# SCH_MCU.net
KiCad netlist of a schematic drawn in Altium Designer
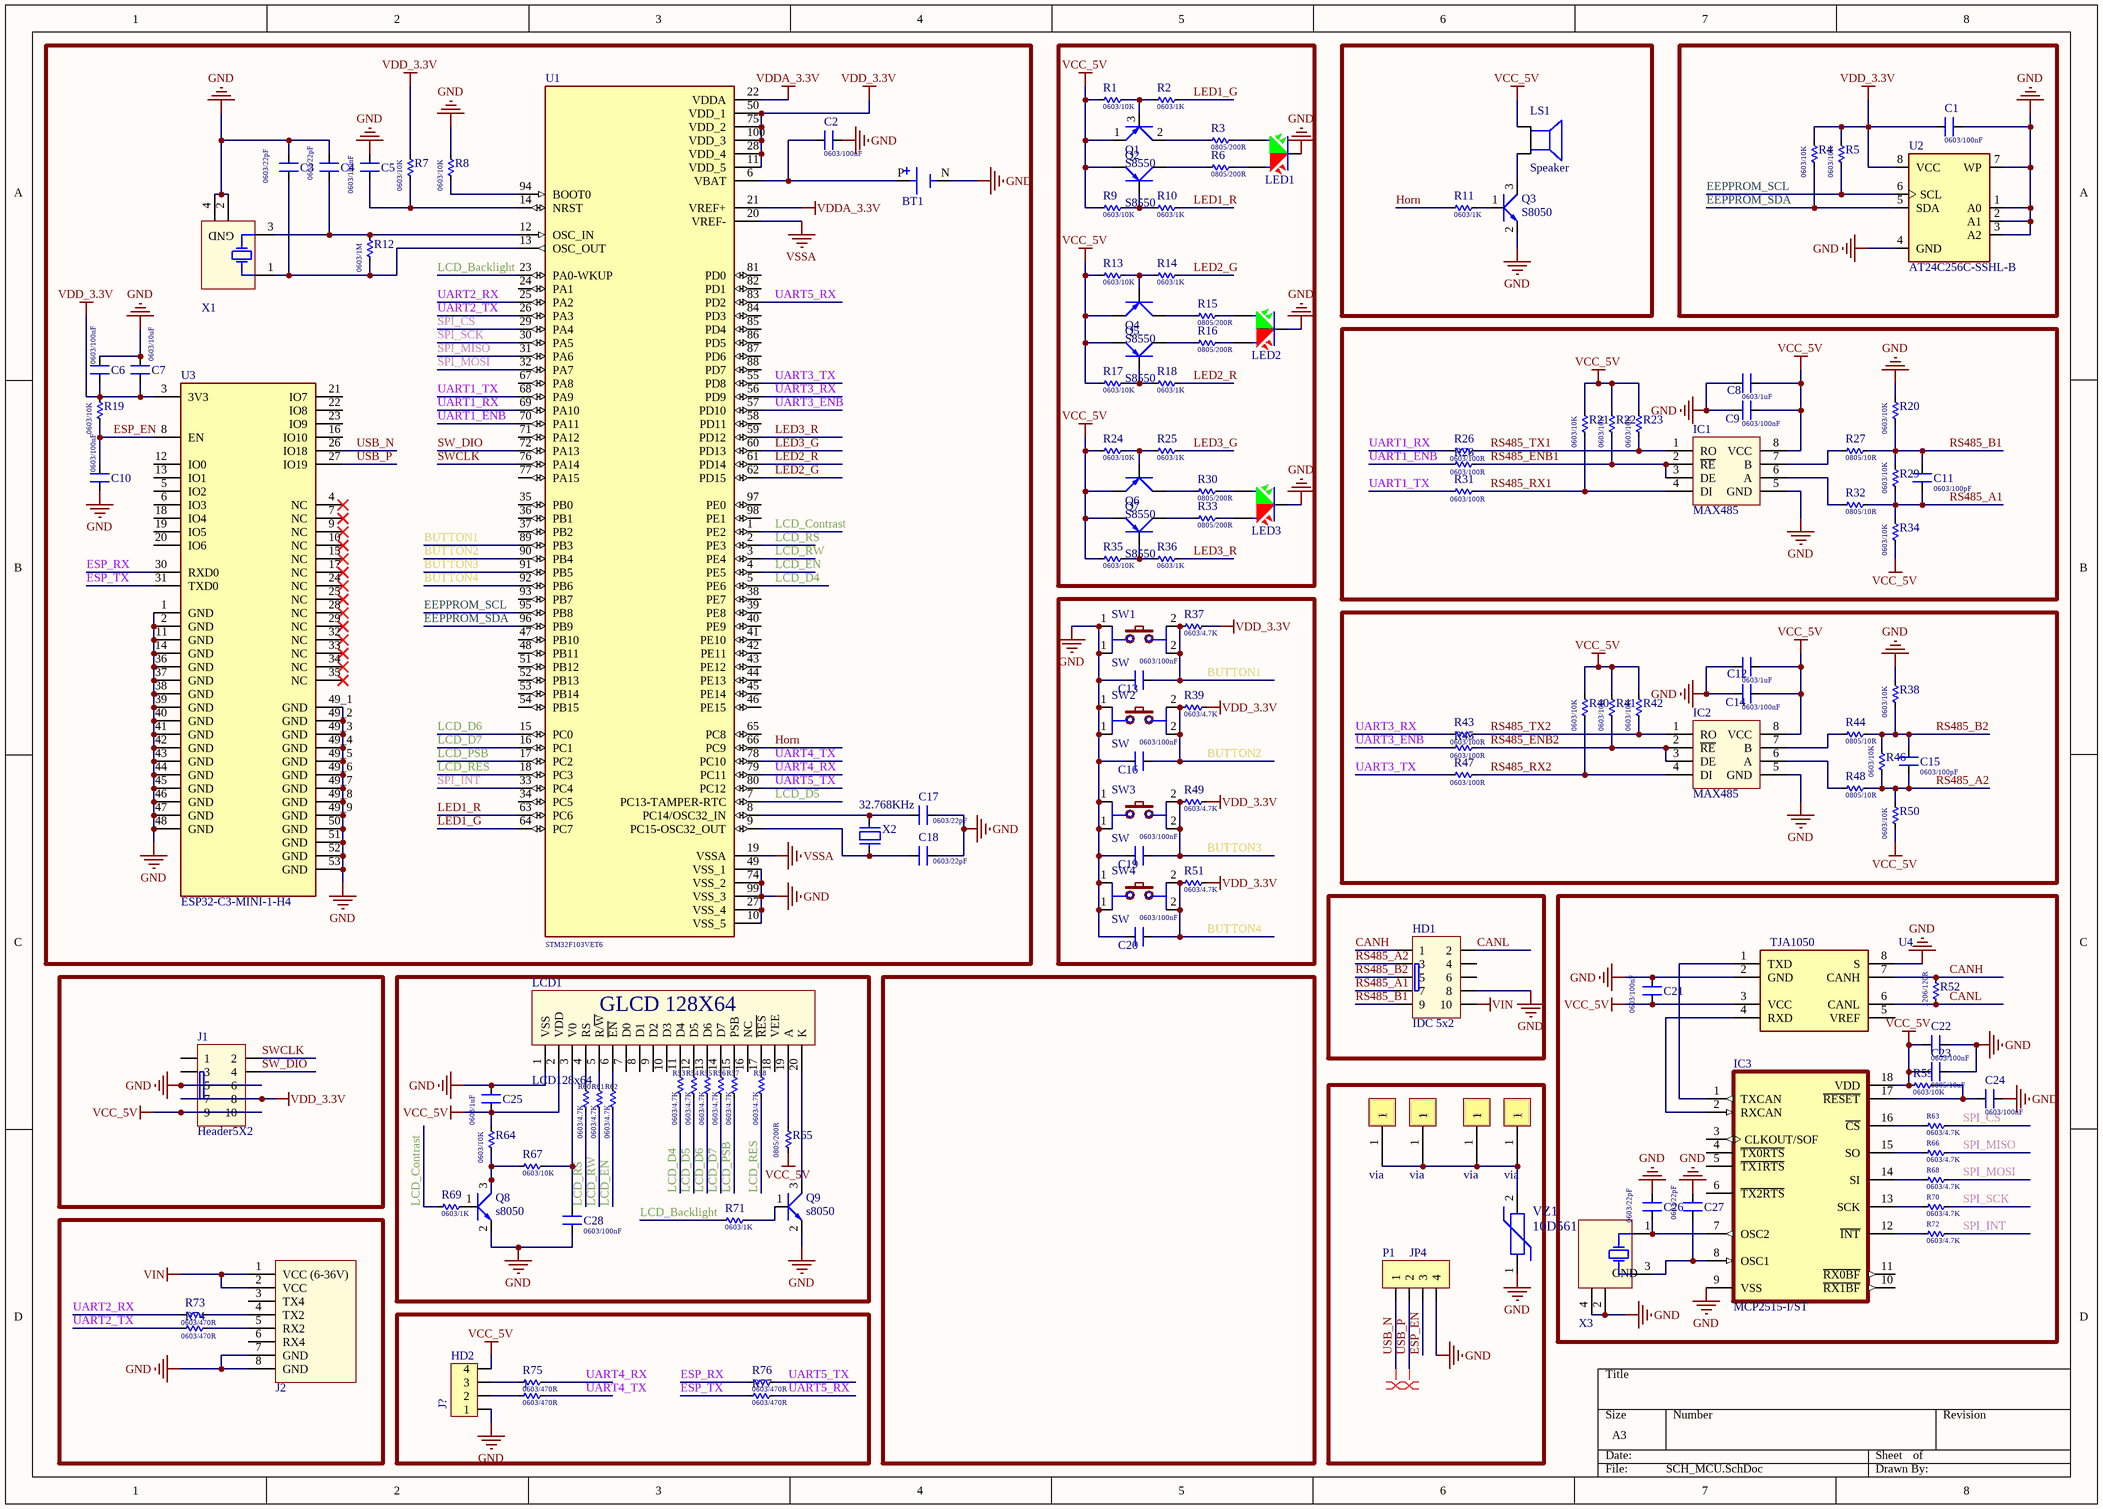
[diagram p0: SCH_MCU.SchDoc]

(export (version "E")
  (design (tool "Eeschema 10.0.6"))
  (components
    (comp (ref "1")
      (value "0603/470R")
      (footprint "RES-SMD-0603")
      (description "Resistor")
      (fields
        (field (name "MANUFACTURER") "Generic Components")
        (field (name "PUBLISHER") "Altium Hobart Technology Centre")
      )
      (libsource (lib "RAL") (part "Res-SMD"))
    )
    (comp (ref "BT1")
      (value "BATTERY")
      (footprint "BAT_CR2032-BS-6-1")
      (description "Battery base CR2032 SMD Battery Connectors ROHS")
      (fields (field (name "MP") "CR2032-BS-6-1") (field (name "MF") "Shenzhen Q&J Electronics Co. Ltd"))
      (libsource (lib "mySche") (part "CR2032-BS-6-1"))
    )
    (comp (ref "C1") (value "0603/100nF") (footprint "CAP-SMD-0603") (libsource (lib "RAL") (part "CAP-SMD")))
    (comp (ref "C2") (value "0603/100nF") (footprint "CAP-SMD-0603") (libsource (lib "RAL") (part "CAP-SMD")))
    (comp (ref "C3") (value "0603/22pF") (footprint "CAP-SMD-0603") (libsource (lib "RAL") (part "CAP-SMD")))
    (comp (ref "C4") (value "0603/22pF") (footprint "CAP-SMD-0603") (libsource (lib "RAL") (part "CAP-SMD")))
    (comp (ref "C5") (value "0603/100nF") (footprint "CAP-SMD-0603") (libsource (lib "RAL") (part "CAP-SMD")))
    (comp (ref "C6") (value "0603/100nF") (footprint "CAP-SMD-0603") (libsource (lib "RAL") (part "CAP-SMD")))
    (comp (ref "C7") (value "0603/10uF") (footprint "CAP-SMD-0603") (libsource (lib "RAL") (part "CAP-SMD")))
    (comp (ref "C8") (value "0603/1uF") (footprint "CAP-SMD-0603") (libsource (lib "RAL") (part "CAP-SMD")))
    (comp (ref "C9") (value "0603/100nF") (footprint "CAP-SMD-0603") (libsource (lib "RAL") (part "CAP-SMD")))
    (comp (ref "C10")
      (value "0603/100nF")
      (footprint "CAP-SMD-0603")
      (libsource (lib "RAL") (part "CAP-SMD"))
    )
    (comp (ref "C11")
      (value "0603/100pF")
      (footprint "CAP-SMD-0603")
      (libsource (lib "RAL") (part "CAP-SMD"))
    )
    (comp (ref "C12") (value "0603/1uF") (footprint "CAP-SMD-0603") (libsource (lib "RAL") (part "CAP-SMD")))
    (comp (ref "C13")
      (value "0603/100nF")
      (footprint "CAP-SMD-0603")
      (libsource (lib "RAL") (part "CAP-SMD"))
    )
    (comp (ref "C14")
      (value "0603/100nF")
      (footprint "CAP-SMD-0603")
      (libsource (lib "RAL") (part "CAP-SMD"))
    )
    (comp (ref "C15")
      (value "0603/100pF")
      (footprint "CAP-SMD-0603")
      (libsource (lib "RAL") (part "CAP-SMD"))
    )
    (comp (ref "C16")
      (value "0603/100nF")
      (footprint "CAP-SMD-0603")
      (libsource (lib "RAL") (part "CAP-SMD"))
    )
    (comp (ref "C17") (value "0603/22pF") (footprint "CAP-SMD-0603") (libsource (lib "RAL") (part "CAP-SMD")))
    (comp (ref "C18") (value "0603/22pF") (footprint "CAP-SMD-0603") (libsource (lib "RAL") (part "CAP-SMD")))
    (comp (ref "C19")
      (value "0603/100nF")
      (footprint "CAP-SMD-0603")
      (libsource (lib "RAL") (part "CAP-SMD"))
    )
    (comp (ref "C20")
      (value "0603/100nF")
      (footprint "CAP-SMD-0603")
      (libsource (lib "RAL") (part "CAP-SMD"))
    )
    (comp (ref "C21")
      (value "0603/100nF")
      (footprint "CAP-SMD-0603")
      (libsource (lib "RAL") (part "CAP-SMD"))
    )
    (comp (ref "C22")
      (value "0603/100nF")
      (footprint "CAP-SMD-0603")
      (libsource (lib "RAL") (part "CAP-SMD"))
    )
    (comp (ref "C23") (value "0805/10uF") (footprint "CAP-SMD-0805") (libsource (lib "RAL") (part "CAP-SMD")))
    (comp (ref "C24")
      (value "0603/100nF")
      (footprint "CAP-SMD-0603")
      (libsource (lib "RAL") (part "CAP-SMD"))
    )
    (comp (ref "C25") (value "0603/1uF") (footprint "CAP-SMD-0603") (libsource (lib "RAL") (part "CAP-SMD")))
    (comp (ref "C26") (value "0603/22pF") (footprint "CAP-SMD-0603") (libsource (lib "RAL") (part "CAP-SMD")))
    (comp (ref "C27") (value "0603/22pF") (footprint "CAP-SMD-0603") (libsource (lib "RAL") (part "CAP-SMD")))
    (comp (ref "C28")
      (value "0603/100nF")
      (footprint "CAP-SMD-0603")
      (libsource (lib "RAL") (part "CAP-SMD"))
    )
    (comp (ref "HD1")
      (value "IDC 5x2")
      (footprint "IDC10-BH")
      (libsource (lib "TechMT.VN_Lib_Project v2") (part "IDC 5X2"))
    )
    (comp (ref "HD2")
      (value "J?")
      (footprint "Header4")
      (description "Header IDC, 4 x 1 Pin Vertical 2.54mm Pitch (Non-Boxed, Male)")
      (fields
        (field (name "MANUFACTURER") "Würth Elektronik eiSos GmbH")
        (field (name "PARTNO") "613002143121")
        (field (name "CREATED BY") "Karrer Zheng")
      )
      (libsource (lib "TechMT.VN_Lib_Project v2") (part "Header4"))
    )
    (comp (ref "IC1")
      (value "MAX485")
      (footprint "SO8")
      (description "RS232 - RS485 (Same sn75176)")
      (libsource (lib "RAL") (part "IC MAX485"))
    )
    (comp (ref "IC2")
      (value "MAX485")
      (footprint "SO8")
      (description "RS232 - RS485 (Same sn75176)")
      (libsource (lib "RAL") (part "IC MAX485"))
    )
    (comp (ref "IC3")
      (value "MCP2515-I/ST")
      (footprint "SO18")
      (description "CAN 1Mbps Sleep/Standby 3.3V/5V 20-Pin TSSOP Tube")
      (fields (field (name "MF") "Microchip Technology"))
      (libsource (lib "lib") (part "MCP2515-I/ST"))
    )
    (comp (ref "J1") (value "Header5X2") (footprint "IDC10-BH") (libsource (lib "RAL") (part "Header5X2")))
    (comp (ref "J2") (value "8pin_2mm") (footprint "8PIN_2mm") (libsource (lib "mySche") (part "8pin_2mm")))
    (comp (ref "LCD1")
      (value "LCD128x64")
      (footprint "LCD128X64 ST7920")
      (description "LCD Graphic 128x64")
      (libsource (lib "lib") (part "LCD128x64"))
    )
    (comp (ref "LED1")
      (value "LED")
      (footprint "LED-32")
      (description "LED 2 colour Green and Red")
      (libsource (lib "RAL") (part "LED2"))
    )
    (comp (ref "LED2")
      (value "LED")
      (footprint "LED-32")
      (description "LED 2 colour Green and Red")
      (libsource (lib "RAL") (part "LED2"))
    )
    (comp (ref "LED3")
      (value "LED")
      (footprint "LED-32")
      (description "LED 2 colour Green and Red")
      (libsource (lib "RAL") (part "LED2"))
    )
    (comp (ref "LS1")
      (value "Speaker")
      (footprint "SPEAKER - 9*5.5")
      (description "Loudspeaker")
      (fields (field (name "PUBLISHER") "Altium Limited"))
      (libsource (lib "RAL") (part "Speaker"))
    )
    (comp (ref "P1")
      (value "JP4")
      (footprint "JP4-C1T")
      (description "WR-PHD 2.54 mm Angled Socket Header")
      (fields
        (field (name "MANUFACTURER") "Würth Elektronik eiSos GmbH")
        (field (name "PARTNO") "613004143121")
        (field (name "CREATED BY") "Karrer Zheng")
      )
      (libsource (lib "RAL") (part "JP4"))
    )
    (comp (ref "Q1")
      (value "S8550")
      (footprint "SOT23-321")
      (description "PNP 600mW, ECB")
      (libsource (lib "RAL") (part "BJT PNP"))
    )
    (comp (ref "Q2")
      (value "S8550")
      (footprint "SOT23-321")
      (description "PNP 600mW, ECB")
      (libsource (lib "") (part "BJT PNP_1"))
    )
    (comp (ref "Q3")
      (value "S8050")
      (footprint "SOT23-132")
      (description "NPN 600mW, ECB")
      (libsource (lib "RAL") (part "BJT NPN"))
    )
    (comp (ref "Q4")
      (value "S8550")
      (footprint "SOT23-321")
      (description "PNP 600mW, ECB")
      (libsource (lib "") (part "BJT PNP_1"))
    )
    (comp (ref "Q5")
      (value "S8550")
      (footprint "SOT23-321")
      (description "PNP 600mW, ECB")
      (libsource (lib "") (part "BJT PNP_1"))
    )
    (comp (ref "Q6")
      (value "S8550")
      (footprint "SOT23-321")
      (description "PNP 600mW, ECB")
      (libsource (lib "") (part "BJT PNP_1"))
    )
    (comp (ref "Q7")
      (value "S8550")
      (footprint "SOT23-321")
      (description "PNP 600mW, ECB")
      (libsource (lib "") (part "BJT PNP_1"))
    )
    (comp (ref "Q8")
      (value "s8050")
      (footprint "SOT23-132")
      (description "NPN 600mW, ECB")
      (libsource (lib "RAL") (part "BJT NPN"))
    )
    (comp (ref "Q9")
      (value "s8050")
      (footprint "SOT23-132")
      (description "NPN 600mW, ECB")
      (libsource (lib "RAL") (part "BJT NPN"))
    )
    (comp (ref "R1")
      (value "0603/10K")
      (footprint "RES-SMD-0603")
      (description "Resistor")
      (fields
        (field (name "MANUFACTURER") "Generic Components")
        (field (name "PUBLISHER") "Altium Hobart Technology Centre")
      )
      (libsource (lib "RAL") (part "Res-SMD"))
    )
    (comp (ref "R2")
      (value "0603/1K")
      (footprint "RES-SMD-0603")
      (description "Resistor")
      (fields
        (field (name "MANUFACTURER") "Generic Components")
        (field (name "PUBLISHER") "Altium Hobart Technology Centre")
      )
      (libsource (lib "RAL") (part "Res-SMD"))
    )
    (comp (ref "R3")
      (value "0805/200R")
      (footprint "RES-SMD-0805")
      (description "Resistor")
      (fields
        (field (name "MANUFACTURER") "Generic Components")
        (field (name "PUBLISHER") "Altium Hobart Technology Centre")
      )
      (libsource (lib "RAL") (part "Res-SMD"))
    )
    (comp (ref "R4")
      (value "0603/10K")
      (footprint "RES-SMD-0603")
      (description "Resistor")
      (fields
        (field (name "MANUFACTURER") "Generic Components")
        (field (name "PUBLISHER") "Altium Hobart Technology Centre")
      )
      (libsource (lib "RAL") (part "Res-SMD"))
    )
    (comp (ref "R5")
      (value "0603/10K")
      (footprint "RES-SMD-0603")
      (description "Resistor")
      (fields
        (field (name "MANUFACTURER") "Generic Components")
        (field (name "PUBLISHER") "Altium Hobart Technology Centre")
      )
      (libsource (lib "RAL") (part "Res-SMD"))
    )
    (comp (ref "R6")
      (value "0805/200R")
      (footprint "RES-SMD-0805")
      (description "Resistor")
      (fields
        (field (name "MANUFACTURER") "Generic Components")
        (field (name "PUBLISHER") "Altium Hobart Technology Centre")
      )
      (libsource (lib "RAL") (part "Res-SMD"))
    )
    (comp (ref "R7")
      (value "0603/10K")
      (footprint "RES-SMD-0603")
      (description "Resistor")
      (fields
        (field (name "MANUFACTURER") "Generic Components")
        (field (name "PUBLISHER") "Altium Hobart Technology Centre")
      )
      (libsource (lib "RAL") (part "Res-SMD"))
    )
    (comp (ref "R8")
      (value "0603/10K")
      (footprint "RES-SMD-0603")
      (description "Resistor")
      (fields
        (field (name "MANUFACTURER") "Generic Components")
        (field (name "PUBLISHER") "Altium Hobart Technology Centre")
      )
      (libsource (lib "RAL") (part "Res-SMD"))
    )
    (comp (ref "R9")
      (value "0603/10K")
      (footprint "RES-SMD-0603")
      (description "Resistor")
      (fields
        (field (name "MANUFACTURER") "Generic Components")
        (field (name "PUBLISHER") "Altium Hobart Technology Centre")
      )
      (libsource (lib "RAL") (part "Res-SMD"))
    )
    (comp (ref "R10")
      (value "0603/1K")
      (footprint "RES-SMD-0603")
      (description "Resistor")
      (fields
        (field (name "MANUFACTURER") "Generic Components")
        (field (name "PUBLISHER") "Altium Hobart Technology Centre")
      )
      (libsource (lib "RAL") (part "Res-SMD"))
    )
    (comp (ref "R11")
      (value "0603/1K")
      (footprint "RES-SMD-0603")
      (description "Resistor")
      (fields
        (field (name "MANUFACTURER") "Generic Components")
        (field (name "PUBLISHER") "Altium Hobart Technology Centre")
      )
      (libsource (lib "RAL") (part "Res-SMD"))
    )
    (comp (ref "R12")
      (value "0603/1M")
      (footprint "RES-SMD-0603")
      (description "Resistor")
      (fields
        (field (name "MANUFACTURER") "Generic Components")
        (field (name "PUBLISHER") "Altium Hobart Technology Centre")
      )
      (libsource (lib "RAL") (part "Res-SMD"))
    )
    (comp (ref "R13")
      (value "0603/10K")
      (footprint "RES-SMD-0603")
      (description "Resistor")
      (fields
        (field (name "MANUFACTURER") "Generic Components")
        (field (name "PUBLISHER") "Altium Hobart Technology Centre")
      )
      (libsource (lib "RAL") (part "Res-SMD"))
    )
    (comp (ref "R14")
      (value "0603/1K")
      (footprint "RES-SMD-0603")
      (description "Resistor")
      (fields
        (field (name "MANUFACTURER") "Generic Components")
        (field (name "PUBLISHER") "Altium Hobart Technology Centre")
      )
      (libsource (lib "RAL") (part "Res-SMD"))
    )
    (comp (ref "R15")
      (value "0805/200R")
      (footprint "RES-SMD-0805")
      (description "Resistor")
      (fields
        (field (name "MANUFACTURER") "Generic Components")
        (field (name "PUBLISHER") "Altium Hobart Technology Centre")
      )
      (libsource (lib "RAL") (part "Res-SMD"))
    )
    (comp (ref "R16")
      (value "0805/200R")
      (footprint "RES-SMD-0805")
      (description "Resistor")
      (fields
        (field (name "MANUFACTURER") "Generic Components")
        (field (name "PUBLISHER") "Altium Hobart Technology Centre")
      )
      (libsource (lib "RAL") (part "Res-SMD"))
    )
    (comp (ref "R17")
      (value "0603/10K")
      (footprint "RES-SMD-0603")
      (description "Resistor")
      (fields
        (field (name "MANUFACTURER") "Generic Components")
        (field (name "PUBLISHER") "Altium Hobart Technology Centre")
      )
      (libsource (lib "RAL") (part "Res-SMD"))
    )
    (comp (ref "R18")
      (value "0603/1K")
      (footprint "RES-SMD-0603")
      (description "Resistor")
      (fields
        (field (name "MANUFACTURER") "Generic Components")
        (field (name "PUBLISHER") "Altium Hobart Technology Centre")
      )
      (libsource (lib "RAL") (part "Res-SMD"))
    )
    (comp (ref "R19")
      (value "0603/10K")
      (footprint "RES-SMD-0603")
      (description "Resistor")
      (fields
        (field (name "MANUFACTURER") "Generic Components")
        (field (name "PUBLISHER") "Altium Hobart Technology Centre")
      )
      (libsource (lib "RAL") (part "Res-SMD"))
    )
    (comp (ref "R20")
      (value "0603/10K")
      (footprint "RES-SMD-0603")
      (description "Resistor")
      (fields
        (field (name "MANUFACTURER") "Generic Components")
        (field (name "PUBLISHER") "Altium Hobart Technology Centre")
      )
      (libsource (lib "RAL") (part "Res-SMD"))
    )
    (comp (ref "R21")
      (value "0603/10K")
      (footprint "RES-SMD-0603")
      (description "Resistor")
      (fields
        (field (name "MANUFACTURER") "Generic Components")
        (field (name "PUBLISHER") "Altium Hobart Technology Centre")
      )
      (libsource (lib "RAL") (part "Res-SMD"))
    )
    (comp (ref "R22")
      (value "0603/10K")
      (footprint "RES-SMD-0603")
      (description "Resistor")
      (fields
        (field (name "MANUFACTURER") "Generic Components")
        (field (name "PUBLISHER") "Altium Hobart Technology Centre")
      )
      (libsource (lib "RAL") (part "Res-SMD"))
    )
    (comp (ref "R23")
      (value "0603/10K")
      (footprint "RES-SMD-0603")
      (description "Resistor")
      (fields
        (field (name "MANUFACTURER") "Generic Components")
        (field (name "PUBLISHER") "Altium Hobart Technology Centre")
      )
      (libsource (lib "RAL") (part "Res-SMD"))
    )
    (comp (ref "R24")
      (value "0603/10K")
      (footprint "RES-SMD-0603")
      (description "Resistor")
      (fields
        (field (name "MANUFACTURER") "Generic Components")
        (field (name "PUBLISHER") "Altium Hobart Technology Centre")
      )
      (libsource (lib "RAL") (part "Res-SMD"))
    )
    (comp (ref "R25")
      (value "0603/1K")
      (footprint "RES-SMD-0603")
      (description "Resistor")
      (fields
        (field (name "MANUFACTURER") "Generic Components")
        (field (name "PUBLISHER") "Altium Hobart Technology Centre")
      )
      (libsource (lib "RAL") (part "Res-SMD"))
    )
    (comp (ref "R26")
      (value "0603/100R")
      (footprint "RES-SMD-0603")
      (description "Resistor")
      (fields
        (field (name "MANUFACTURER") "Generic Components")
        (field (name "PUBLISHER") "Altium Hobart Technology Centre")
      )
      (libsource (lib "RAL") (part "Res-SMD"))
    )
    (comp (ref "R27")
      (value "0805/10R")
      (footprint "RES-SMD-0805")
      (description "Resistor")
      (fields
        (field (name "MANUFACTURER") "Generic Components")
        (field (name "PUBLISHER") "Altium Hobart Technology Centre")
      )
      (libsource (lib "RAL") (part "Res-SMD"))
    )
    (comp (ref "R28")
      (value "0603/100R")
      (footprint "RES-SMD-0603")
      (description "Resistor")
      (fields
        (field (name "MANUFACTURER") "Generic Components")
        (field (name "PUBLISHER") "Altium Hobart Technology Centre")
      )
      (libsource (lib "RAL") (part "Res-SMD"))
    )
    (comp (ref "R29")
      (value "0603/10K")
      (footprint "RES-SMD-0603")
      (description "Resistor")
      (fields
        (field (name "MANUFACTURER") "Generic Components")
        (field (name "PUBLISHER") "Altium Hobart Technology Centre")
      )
      (libsource (lib "RAL") (part "Res-SMD"))
    )
    (comp (ref "R30")
      (value "0805/200R")
      (footprint "RES-SMD-0805")
      (description "Resistor")
      (fields
        (field (name "MANUFACTURER") "Generic Components")
        (field (name "PUBLISHER") "Altium Hobart Technology Centre")
      )
      (libsource (lib "RAL") (part "Res-SMD"))
    )
    (comp (ref "R31")
      (value "0603/100R")
      (footprint "RES-SMD-0603")
      (description "Resistor")
      (fields
        (field (name "MANUFACTURER") "Generic Components")
        (field (name "PUBLISHER") "Altium Hobart Technology Centre")
      )
      (libsource (lib "RAL") (part "Res-SMD"))
    )
    (comp (ref "R32")
      (value "0805/10R")
      (footprint "RES-SMD-0805")
      (description "Resistor")
      (fields
        (field (name "MANUFACTURER") "Generic Components")
        (field (name "PUBLISHER") "Altium Hobart Technology Centre")
      )
      (libsource (lib "RAL") (part "Res-SMD"))
    )
    (comp (ref "R33")
      (value "0805/200R")
      (footprint "RES-SMD-0805")
      (description "Resistor")
      (fields
        (field (name "MANUFACTURER") "Generic Components")
        (field (name "PUBLISHER") "Altium Hobart Technology Centre")
      )
      (libsource (lib "RAL") (part "Res-SMD"))
    )
    (comp (ref "R34")
      (value "0603/10K")
      (footprint "RES-SMD-0603")
      (description "Resistor")
      (fields
        (field (name "MANUFACTURER") "Generic Components")
        (field (name "PUBLISHER") "Altium Hobart Technology Centre")
      )
      (libsource (lib "RAL") (part "Res-SMD"))
    )
    (comp (ref "R35")
      (value "0603/10K")
      (footprint "RES-SMD-0603")
      (description "Resistor")
      (fields
        (field (name "MANUFACTURER") "Generic Components")
        (field (name "PUBLISHER") "Altium Hobart Technology Centre")
      )
      (libsource (lib "RAL") (part "Res-SMD"))
    )
    (comp (ref "R36")
      (value "0603/1K")
      (footprint "RES-SMD-0603")
      (description "Resistor")
      (fields
        (field (name "MANUFACTURER") "Generic Components")
        (field (name "PUBLISHER") "Altium Hobart Technology Centre")
      )
      (libsource (lib "RAL") (part "Res-SMD"))
    )
    (comp (ref "R37")
      (value "0603/4.7K")
      (footprint "RES-SMD-0603")
      (description "Resistor")
      (fields
        (field (name "MANUFACTURER") "Generic Components")
        (field (name "PUBLISHER") "Altium Hobart Technology Centre")
      )
      (libsource (lib "RAL") (part "Res-SMD"))
    )
    (comp (ref "R38")
      (value "0603/10K")
      (footprint "RES-SMD-0603")
      (description "Resistor")
      (fields
        (field (name "MANUFACTURER") "Generic Components")
        (field (name "PUBLISHER") "Altium Hobart Technology Centre")
      )
      (libsource (lib "RAL") (part "Res-SMD"))
    )
    (comp (ref "R39")
      (value "0603/4.7K")
      (footprint "RES-SMD-0603")
      (description "Resistor")
      (fields
        (field (name "MANUFACTURER") "Generic Components")
        (field (name "PUBLISHER") "Altium Hobart Technology Centre")
      )
      (libsource (lib "RAL") (part "Res-SMD"))
    )
    (comp (ref "R40")
      (value "0603/10K")
      (footprint "RES-SMD-0603")
      (description "Resistor")
      (fields
        (field (name "MANUFACTURER") "Generic Components")
        (field (name "PUBLISHER") "Altium Hobart Technology Centre")
      )
      (libsource (lib "RAL") (part "Res-SMD"))
    )
    (comp (ref "R41")
      (value "0603/10K")
      (footprint "RES-SMD-0603")
      (description "Resistor")
      (fields
        (field (name "MANUFACTURER") "Generic Components")
        (field (name "PUBLISHER") "Altium Hobart Technology Centre")
      )
      (libsource (lib "RAL") (part "Res-SMD"))
    )
    (comp (ref "R42")
      (value "0603/10K")
      (footprint "RES-SMD-0603")
      (description "Resistor")
      (fields
        (field (name "MANUFACTURER") "Generic Components")
        (field (name "PUBLISHER") "Altium Hobart Technology Centre")
      )
      (libsource (lib "RAL") (part "Res-SMD"))
    )
    (comp (ref "R43")
      (value "0603/100R")
      (footprint "RES-SMD-0603")
      (description "Resistor")
      (fields
        (field (name "MANUFACTURER") "Generic Components")
        (field (name "PUBLISHER") "Altium Hobart Technology Centre")
      )
      (libsource (lib "RAL") (part "Res-SMD"))
    )
    (comp (ref "R44")
      (value "0805/10R")
      (footprint "RES-SMD-0805")
      (description "Resistor")
      (fields
        (field (name "MANUFACTURER") "Generic Components")
        (field (name "PUBLISHER") "Altium Hobart Technology Centre")
      )
      (libsource (lib "RAL") (part "Res-SMD"))
    )
    (comp (ref "R45")
      (value "0603/100R")
      (footprint "RES-SMD-0603")
      (description "Resistor")
      (fields
        (field (name "MANUFACTURER") "Generic Components")
        (field (name "PUBLISHER") "Altium Hobart Technology Centre")
      )
      (libsource (lib "RAL") (part "Res-SMD"))
    )
    (comp (ref "R46")
      (value "0603/10K")
      (footprint "RES-SMD-0603")
      (description "Resistor")
      (fields
        (field (name "MANUFACTURER") "Generic Components")
        (field (name "PUBLISHER") "Altium Hobart Technology Centre")
      )
      (libsource (lib "RAL") (part "Res-SMD"))
    )
    (comp (ref "R47")
      (value "0603/100R")
      (footprint "RES-SMD-0603")
      (description "Resistor")
      (fields
        (field (name "MANUFACTURER") "Generic Components")
        (field (name "PUBLISHER") "Altium Hobart Technology Centre")
      )
      (libsource (lib "RAL") (part "Res-SMD"))
    )
    (comp (ref "R48")
      (value "0805/10R")
      (footprint "RES-SMD-0805")
      (description "Resistor")
      (fields
        (field (name "MANUFACTURER") "Generic Components")
        (field (name "PUBLISHER") "Altium Hobart Technology Centre")
      )
      (libsource (lib "RAL") (part "Res-SMD"))
    )
    (comp (ref "R49")
      (value "0603/4.7K")
      (footprint "RES-SMD-0603")
      (description "Resistor")
      (fields
        (field (name "MANUFACTURER") "Generic Components")
        (field (name "PUBLISHER") "Altium Hobart Technology Centre")
      )
      (libsource (lib "RAL") (part "Res-SMD"))
    )
    (comp (ref "R50")
      (value "0603/10K")
      (footprint "RES-SMD-0603")
      (description "Resistor")
      (fields
        (field (name "MANUFACTURER") "Generic Components")
        (field (name "PUBLISHER") "Altium Hobart Technology Centre")
      )
      (libsource (lib "RAL") (part "Res-SMD"))
    )
    (comp (ref "R51")
      (value "0603/4.7K")
      (footprint "RES-SMD-0603")
      (description "Resistor")
      (fields
        (field (name "MANUFACTURER") "Generic Components")
        (field (name "PUBLISHER") "Altium Hobart Technology Centre")
      )
      (libsource (lib "RAL") (part "Res-SMD"))
    )
    (comp (ref "R52")
      (value "1206/120R")
      (footprint "RES-SMD-0603")
      (description "Resistor")
      (fields
        (field (name "MANUFACTURER") "Generic Components")
        (field (name "PUBLISHER") "Altium Hobart Technology Centre")
      )
      (libsource (lib "RAL") (part "Res-SMD"))
    )
    (comp (ref "R53")
      (value "0603/4.7K")
      (footprint "RES-SMD-0603")
      (description "Resistor")
      (fields
        (field (name "MANUFACTURER") "Generic Components")
        (field (name "PUBLISHER") "Altium Hobart Technology Centre")
      )
      (libsource (lib "RAL") (part "Res-SMD"))
    )
    (comp (ref "R54")
      (value "0603/4.7K")
      (footprint "RES-SMD-0603")
      (description "Resistor")
      (fields
        (field (name "MANUFACTURER") "Generic Components")
        (field (name "PUBLISHER") "Altium Hobart Technology Centre")
      )
      (libsource (lib "RAL") (part "Res-SMD"))
    )
    (comp (ref "R55")
      (value "0603/4.7K")
      (footprint "RES-SMD-0603")
      (description "Resistor")
      (fields
        (field (name "MANUFACTURER") "Generic Components")
        (field (name "PUBLISHER") "Altium Hobart Technology Centre")
      )
      (libsource (lib "RAL") (part "Res-SMD"))
    )
    (comp (ref "R56")
      (value "0603/4.7K")
      (footprint "RES-SMD-0603")
      (description "Resistor")
      (fields
        (field (name "MANUFACTURER") "Generic Components")
        (field (name "PUBLISHER") "Altium Hobart Technology Centre")
      )
      (libsource (lib "RAL") (part "Res-SMD"))
    )
    (comp (ref "R57")
      (value "0603/4.7K")
      (footprint "RES-SMD-0603")
      (description "Resistor")
      (fields
        (field (name "MANUFACTURER") "Generic Components")
        (field (name "PUBLISHER") "Altium Hobart Technology Centre")
      )
      (libsource (lib "RAL") (part "Res-SMD"))
    )
    (comp (ref "R58")
      (value "0603/4.7K")
      (footprint "RES-SMD-0603")
      (description "Resistor")
      (fields
        (field (name "MANUFACTURER") "Generic Components")
        (field (name "PUBLISHER") "Altium Hobart Technology Centre")
      )
      (libsource (lib "RAL") (part "Res-SMD"))
    )
    (comp (ref "R59")
      (value "0603/10K")
      (footprint "RES-SMD-0603")
      (description "Resistor")
      (fields
        (field (name "MANUFACTURER") "Generic Components")
        (field (name "PUBLISHER") "Altium Hobart Technology Centre")
      )
      (libsource (lib "RAL") (part "Res-SMD"))
    )
    (comp (ref "R60")
      (value "0603/4.7K")
      (footprint "RES-SMD-0603")
      (description "Resistor")
      (fields
        (field (name "MANUFACTURER") "Generic Components")
        (field (name "PUBLISHER") "Altium Hobart Technology Centre")
      )
      (libsource (lib "RAL") (part "Res-SMD"))
    )
    (comp (ref "R61")
      (value "0603/4.7K")
      (footprint "RES-SMD-0603")
      (description "Resistor")
      (fields
        (field (name "MANUFACTURER") "Generic Components")
        (field (name "PUBLISHER") "Altium Hobart Technology Centre")
      )
      (libsource (lib "RAL") (part "Res-SMD"))
    )
    (comp (ref "R62")
      (value "0603/4.7K")
      (footprint "RES-SMD-0603")
      (description "Resistor")
      (fields
        (field (name "MANUFACTURER") "Generic Components")
        (field (name "PUBLISHER") "Altium Hobart Technology Centre")
      )
      (libsource (lib "RAL") (part "Res-SMD"))
    )
    (comp (ref "R63")
      (value "0603/4.7K")
      (footprint "RES-SMD-0603")
      (description "Resistor")
      (fields
        (field (name "MANUFACTURER") "Generic Components")
        (field (name "PUBLISHER") "Altium Hobart Technology Centre")
      )
      (libsource (lib "RAL") (part "Res-SMD"))
    )
    (comp (ref "R64")
      (value "0603/10K")
      (footprint "RES-SMD-0603")
      (description "Resistor")
      (fields
        (field (name "MANUFACTURER") "Generic Components")
        (field (name "PUBLISHER") "Altium Hobart Technology Centre")
      )
      (libsource (lib "RAL") (part "Res-SMD"))
    )
    (comp (ref "R65")
      (value "0805/200R")
      (footprint "RES-SMD-0805")
      (description "Resistor")
      (fields
        (field (name "MANUFACTURER") "Generic Components")
        (field (name "PUBLISHER") "Altium Hobart Technology Centre")
      )
      (libsource (lib "RAL") (part "Res-SMD"))
    )
    (comp (ref "R66")
      (value "0603/4.7K")
      (footprint "RES-SMD-0603")
      (description "Resistor")
      (fields
        (field (name "MANUFACTURER") "Generic Components")
        (field (name "PUBLISHER") "Altium Hobart Technology Centre")
      )
      (libsource (lib "RAL") (part "Res-SMD"))
    )
    (comp (ref "R67")
      (value "0603/10K")
      (footprint "RES-SMD-0603")
      (description "Resistor")
      (fields
        (field (name "MANUFACTURER") "Generic Components")
        (field (name "PUBLISHER") "Altium Hobart Technology Centre")
      )
      (libsource (lib "RAL") (part "Res-SMD"))
    )
    (comp (ref "R68")
      (value "0603/4.7K")
      (footprint "RES-SMD-0603")
      (description "Resistor")
      (fields
        (field (name "MANUFACTURER") "Generic Components")
        (field (name "PUBLISHER") "Altium Hobart Technology Centre")
      )
      (libsource (lib "RAL") (part "Res-SMD"))
    )
    (comp (ref "R69")
      (value "0603/1K")
      (footprint "RES-SMD-0603")
      (description "Resistor")
      (fields
        (field (name "MANUFACTURER") "Generic Components")
        (field (name "PUBLISHER") "Altium Hobart Technology Centre")
      )
      (libsource (lib "RAL") (part "Res-SMD"))
    )
    (comp (ref "R70")
      (value "0603/4.7K")
      (footprint "RES-SMD-0603")
      (description "Resistor")
      (fields
        (field (name "MANUFACTURER") "Generic Components")
        (field (name "PUBLISHER") "Altium Hobart Technology Centre")
      )
      (libsource (lib "RAL") (part "Res-SMD"))
    )
    (comp (ref "R71")
      (value "0603/1K")
      (footprint "RES-SMD-0603")
      (description "Resistor")
      (fields
        (field (name "MANUFACTURER") "Generic Components")
        (field (name "PUBLISHER") "Altium Hobart Technology Centre")
      )
      (libsource (lib "RAL") (part "Res-SMD"))
    )
    (comp (ref "R72")
      (value "0603/4.7K")
      (footprint "RES-SMD-0603")
      (description "Resistor")
      (fields
        (field (name "MANUFACTURER") "Generic Components")
        (field (name "PUBLISHER") "Altium Hobart Technology Centre")
      )
      (libsource (lib "RAL") (part "Res-SMD"))
    )
    (comp (ref "R73")
      (value "0603/470R")
      (footprint "RES-SMD-0603")
      (description "Resistor")
      (fields
        (field (name "MANUFACTURER") "Generic Components")
        (field (name "PUBLISHER") "Altium Hobart Technology Centre")
      )
      (libsource (lib "RAL") (part "Res-SMD"))
    )
    (comp (ref "R74")
      (value "0603/470R")
      (footprint "RES-SMD-0603")
      (description "Resistor")
      (fields
        (field (name "MANUFACTURER") "Generic Components")
        (field (name "PUBLISHER") "Altium Hobart Technology Centre")
      )
      (libsource (lib "RAL") (part "Res-SMD"))
    )
    (comp (ref "R75")
      (value "0603/470R")
      (footprint "RES-SMD-0603")
      (description "Resistor")
      (fields
        (field (name "MANUFACTURER") "Generic Components")
        (field (name "PUBLISHER") "Altium Hobart Technology Centre")
      )
      (libsource (lib "RAL") (part "Res-SMD"))
    )
    (comp (ref "R76")
      (value "0603/470R")
      (footprint "RES-SMD-0603")
      (description "Resistor")
      (fields
        (field (name "MANUFACTURER") "Generic Components")
        (field (name "PUBLISHER") "Altium Hobart Technology Centre")
      )
      (libsource (lib "RAL") (part "Res-SMD"))
    )
    (comp (ref "R77")
      (value "0603/470R")
      (footprint "RES-SMD-0603")
      (description "Resistor")
      (fields
        (field (name "MANUFACTURER") "Generic Components")
        (field (name "PUBLISHER") "Altium Hobart Technology Centre")
      )
      (libsource (lib "RAL") (part "Res-SMD"))
    )
    (comp (ref "SW1")
      (value "SW")
      (footprint "BUTTON-12x12")
      (description "Switch button 4 pin")
      (libsource (lib "RAL") (part "SW4"))
    )
    (comp (ref "SW2")
      (value "SW")
      (footprint "BUTTON-12x12")
      (description "Switch button 4 pin")
      (libsource (lib "RAL") (part "SW4"))
    )
    (comp (ref "SW3")
      (value "SW")
      (footprint "BUTTON-12x12")
      (description "Switch button 4 pin")
      (libsource (lib "RAL") (part "SW4"))
    )
    (comp (ref "SW4")
      (value "SW")
      (footprint "BUTTON-12x12")
      (description "Switch button 4 pin")
      (libsource (lib "RAL") (part "SW4"))
    )
    (comp (ref "U1")
      (value "STM32F103VET6")
      (footprint "QFP50P1600X1600X160-100N")
      (description "ARMÂ® CortexÂ®-M3 STM32F1 Microcontroller IC 32-Bit 72MHz 512KB (512K x 8) FLASH 100-LQFP (14x14)")
      (fields (field (name "MF") "STMicroelectronics"))
      (libsource (lib "lib") (part "STM32F103VET6"))
    )
    (comp (ref "U2")
      (value "AT24C256C-SSHL-B")
      (footprint "SO8")
      (description "EEPROM Serial-2Wire 256K-bit 32K x 8 1.8V/2.5V/3.3V/5V Automotive 8-Pin SOIC N Tube")
      (fields (field (name "MF") "Microchip Technology"))
      (libsource (lib "lib") (part "AT24C256C-SSHL-B"))
    )
    (comp (ref "U3")
      (value "ESP32-C3-MINI-1-H4")
      (footprint "ESP32-C3-MINI-1-H4")
      (libsource (lib "RAL") (part "ESP32-C3-MINI-1-H4"))
    )
    (comp (ref "U4")
      (value "TJA1050")
      (footprint "SO8")
      (description "CAN 1MBd Silent 5V Automotive 8-Pin SO T/R")
      (fields (field (name "MF") "NXP Semiconductors"))
      (libsource (lib "lib") (part "TJA1050"))
    )
    (comp (ref "via1") (value "via") (footprint "VIA_LO") (libsource (lib "mySche") (part "Vit oc")))
    (comp (ref "via2") (value "via") (footprint "VIA_LO") (libsource (lib "mySche") (part "Vit oc")))
    (comp (ref "via3") (value "via") (footprint "VIA_LO") (libsource (lib "mySche") (part "Vit oc")))
    (comp (ref "via4") (value "via") (footprint "VIA_LO") (libsource (lib "mySche") (part "Vit oc")))
    (comp (ref "VZ1")
      (value "10D561")
      (footprint "Varistor 7K561 5mm")
      (description "Varistor")
      (fields (field (name "PUBLISHER") "Altium Limited"))
      (libsource (lib "RAL") (part "VAR"))
    )
    (comp (ref "X1")
      (value "16MHz")
      (footprint "XT4-16.000MHz-4_V")
      (description "Crystal, 16 MHz, -30 to 85 degC, 3.2 x 2.5 x 0.9 mm SMD")
      (libsource (lib "RAL") (part "XT4"))
    )
    (comp (ref "X2")
      (value "32.768KHz")
      (footprint "XT2-32.768KHz-2_V")
      (description "Crystal, 32.768 KHz, -40 to 85 degC, 3.2 x 1.5 x 0.9 mm SMD")
      (libsource (lib "RAL") (part "XT2"))
    )
    (comp (ref "X3")
      (value "8MHz")
      (footprint "XT4-16.000MHz-4_V")
      (description "Crystal, 16 MHz, -30 to 85 degC, 3.2 x 2.5 x 0.9 mm SMD")
      (libsource (lib "") (part "XT4_1"))
    )
  )
  (nets
    (net (code "1") (name "/BUTTON1") (class "Default")
      (node (ref "C13") (pin "2") (pinfunction "2_2") (pintype "passive"))
      (node (ref "R37") (pin "1") (pinfunction "1_1") (pintype "passive"))
      (node (ref "SW1") (pin "2") (pinfunction "2_2") (pintype "passive"))
      (node (ref "U1") (pin "89") (pinfunction "PB3_89") (pintype "bidirectional"))
    )
    (net (code "2") (name "/BUTTON2") (class "Default")
      (node (ref "C16") (pin "2") (pinfunction "2_2") (pintype "passive"))
      (node (ref "R39") (pin "1") (pinfunction "1_1") (pintype "passive"))
      (node (ref "SW2") (pin "2") (pinfunction "2_2") (pintype "passive"))
      (node (ref "U1") (pin "90") (pinfunction "PB4_90") (pintype "bidirectional"))
    )
    (net (code "3") (name "/BUTTON3") (class "Default")
      (node (ref "C19") (pin "2") (pinfunction "2_2") (pintype "passive"))
      (node (ref "R49") (pin "1") (pinfunction "1_1") (pintype "passive"))
      (node (ref "SW3") (pin "2") (pinfunction "2_2") (pintype "passive"))
      (node (ref "U1") (pin "91") (pinfunction "PB5_91") (pintype "bidirectional"))
    )
    (net (code "4") (name "/BUTTON4") (class "Default")
      (node (ref "C20") (pin "2") (pinfunction "2_2") (pintype "passive"))
      (node (ref "R51") (pin "1") (pinfunction "1_1") (pintype "passive"))
      (node (ref "SW4") (pin "2") (pinfunction "2_2") (pintype "passive"))
      (node (ref "U1") (pin "92") (pinfunction "PB6_92") (pintype "bidirectional"))
    )
    (net (code "5") (name "/CANH") (class "Default")
      (node (ref "HD1") (pin "1") (pinfunction "1_1") (pintype "passive"))
      (node (ref "R52") (pin "1") (pinfunction "1_1") (pintype "passive"))
      (node (ref "U4") (pin "7") (pinfunction "CANH_7") (pintype "passive"))
    )
    (net (code "6") (name "/CANL") (class "Default")
      (node (ref "HD1") (pin "2") (pinfunction "2_2") (pintype "passive"))
      (node (ref "R52") (pin "2") (pinfunction "2_2") (pintype "passive"))
      (node (ref "U4") (pin "6") (pinfunction "CANL_6") (pintype "passive"))
    )
    (net (code "7") (name "/EEPPROM_SCL") (class "Default")
      (node (ref "R5") (pin "2") (pinfunction "2_2") (pintype "passive"))
      (node (ref "U1") (pin "95") (pinfunction "PB8_95") (pintype "bidirectional"))
      (node (ref "U2") (pin "6") (pinfunction "SCL_6") (pintype "passive"))
    )
    (net (code "8") (name "/EEPPROM_SDA") (class "Default")
      (node (ref "R4") (pin "2") (pinfunction "2_2") (pintype "passive"))
      (node (ref "U1") (pin "96") (pinfunction "PB9_96") (pintype "bidirectional"))
      (node (ref "U2") (pin "5") (pinfunction "SDA_5") (pintype "passive"))
    )
    (net (code "9") (name "/ESP_EN") (class "Default")
      (node (ref "C10") (pin "1") (pinfunction "1_1") (pintype "passive"))
      (node (ref "P1") (pin "3") (pinfunction "3_3") (pintype "passive"))
      (node (ref "R19") (pin "2") (pinfunction "2_2") (pintype "passive"))
      (node (ref "U3") (pin "8") (pinfunction "EN_8") (pintype "passive"))
    )
    (net (code "10") (name "/ESP_RX") (class "Default")
      (node (ref "R76") (pin "1") (pinfunction "1_1") (pintype "passive"))
      (node (ref "U3") (pin "30") (pinfunction "RXD0_30") (pintype "passive"))
    )
    (net (code "11") (name "/ESP_TX") (class "Default")
      (node (ref "R77") (pin "1") (pinfunction "1_1") (pintype "passive"))
      (node (ref "U3") (pin "31") (pinfunction "TXD0_31") (pintype "passive"))
    )
    (net (code "12") (name "/Horn") (class "Default")
      (node (ref "R11") (pin "1") (pinfunction "1_1") (pintype "passive"))
      (node (ref "U1") (pin "66") (pinfunction "PC9_66") (pintype "bidirectional"))
    )
    (net (code "13") (name "/LCD_Backlight") (class "Default")
      (node (ref "R71") (pin "1") (pinfunction "1_1") (pintype "passive"))
      (node (ref "U1") (pin "23") (pinfunction "PA0-WKUP_23") (pintype "bidirectional"))
    )
    (net (code "14") (name "/LCD_Contrast") (class "Default")
      (node (ref "R69") (pin "1") (pinfunction "1_1") (pintype "passive"))
      (node (ref "U1") (pin "1") (pinfunction "PE2_1") (pintype "bidirectional"))
    )
    (net (code "15") (name "/LCD_D4") (class "Default")
      (node (ref "R53") (pin "1") (pinfunction "1_1") (pintype "passive"))
      (node (ref "U1") (pin "5") (pinfunction "PE6_5") (pintype "bidirectional"))
    )
    (net (code "16") (name "/LCD_D5") (class "Default")
      (node (ref "R54") (pin "1") (pinfunction "1_1") (pintype "passive"))
      (node (ref "U1") (pin "7") (pinfunction "PC13-TAMPER-RTC_7") (pintype "bidirectional"))
    )
    (net (code "17") (name "/LCD_D6") (class "Default")
      (node (ref "R55") (pin "1") (pinfunction "1_1") (pintype "passive"))
      (node (ref "U1") (pin "15") (pinfunction "PC0_15") (pintype "bidirectional"))
    )
    (net (code "18") (name "/LCD_D7") (class "Default")
      (node (ref "R56") (pin "1") (pinfunction "1_1") (pintype "passive"))
      (node (ref "U1") (pin "16") (pinfunction "PC1_16") (pintype "bidirectional"))
    )
    (net (code "19") (name "/LCD_EN") (class "Default")
      (node (ref "R62") (pin "1") (pinfunction "1_1") (pintype "passive"))
      (node (ref "U1") (pin "4") (pinfunction "PE5_4") (pintype "bidirectional"))
    )
    (net (code "20") (name "/LCD_PSB") (class "Default")
      (node (ref "R57") (pin "1") (pinfunction "1_1") (pintype "passive"))
      (node (ref "U1") (pin "17") (pinfunction "PC2_17") (pintype "bidirectional"))
    )
    (net (code "21") (name "/LCD_RES") (class "Default")
      (node (ref "R58") (pin "1") (pinfunction "1_1") (pintype "passive"))
      (node (ref "U1") (pin "18") (pinfunction "PC3_18") (pintype "bidirectional"))
    )
    (net (code "22") (name "/LCD_RS") (class "Default")
      (node (ref "R60") (pin "1") (pinfunction "1_1") (pintype "passive"))
      (node (ref "U1") (pin "2") (pinfunction "PE3_2") (pintype "bidirectional"))
    )
    (net (code "23") (name "/LCD_RW") (class "Default")
      (node (ref "R61") (pin "1") (pinfunction "1_1") (pintype "passive"))
      (node (ref "U1") (pin "3") (pinfunction "PE4_3") (pintype "bidirectional"))
    )
    (net (code "24") (name "/LED1_G") (class "Default")
      (node (ref "R2") (pin "2") (pinfunction "2_2") (pintype "passive"))
      (node (ref "U1") (pin "64") (pinfunction "PC7_64") (pintype "bidirectional"))
    )
    (net (code "25") (name "/LED1_R") (class "Default")
      (node (ref "R10") (pin "2") (pinfunction "2_2") (pintype "passive"))
      (node (ref "U1") (pin "63") (pinfunction "PC6_63") (pintype "bidirectional"))
    )
    (net (code "26") (name "/LED2_G") (class "Default")
      (node (ref "R14") (pin "2") (pinfunction "2_2") (pintype "passive"))
      (node (ref "U1") (pin "62") (pinfunction "PD15_62") (pintype "bidirectional"))
    )
    (net (code "27") (name "/LED2_R") (class "Default")
      (node (ref "R18") (pin "2") (pinfunction "2_2") (pintype "passive"))
      (node (ref "U1") (pin "61") (pinfunction "PD14_61") (pintype "bidirectional"))
    )
    (net (code "28") (name "/LED3_G") (class "Default")
      (node (ref "R25") (pin "2") (pinfunction "2_2") (pintype "passive"))
      (node (ref "U1") (pin "60") (pinfunction "PD13_60") (pintype "bidirectional"))
    )
    (net (code "29") (name "/LED3_R") (class "Default")
      (node (ref "R36") (pin "2") (pinfunction "2_2") (pintype "passive"))
      (node (ref "U1") (pin "59") (pinfunction "PD12_59") (pintype "bidirectional"))
    )
    (net (code "30") (name "/RS485_A1") (class "Default")
      (node (ref "C11") (pin "1") (pinfunction "1_1") (pintype "passive"))
      (node (ref "HD1") (pin "7") (pinfunction "7_7") (pintype "passive"))
      (node (ref "R29") (pin "2") (pinfunction "2_2") (pintype "passive"))
      (node (ref "R32") (pin "2") (pinfunction "2_2") (pintype "passive"))
      (node (ref "R34") (pin "1") (pinfunction "1_1") (pintype "passive"))
    )
    (net (code "31") (name "/RS485_A2") (class "Default")
      (node (ref "C15") (pin "1") (pinfunction "1_1") (pintype "passive"))
      (node (ref "HD1") (pin "3") (pinfunction "3_3") (pintype "passive"))
      (node (ref "R46") (pin "2") (pinfunction "2_2") (pintype "passive"))
      (node (ref "R48") (pin "2") (pinfunction "2_2") (pintype "passive"))
      (node (ref "R50") (pin "1") (pinfunction "1_1") (pintype "passive"))
    )
    (net (code "32") (name "/RS485_B1") (class "Default")
      (node (ref "C11") (pin "2") (pinfunction "2_2") (pintype "passive"))
      (node (ref "HD1") (pin "9") (pinfunction "9_9") (pintype "passive"))
      (node (ref "R20") (pin "2") (pinfunction "2_2") (pintype "passive"))
      (node (ref "R27") (pin "2") (pinfunction "2_2") (pintype "passive"))
      (node (ref "R29") (pin "1") (pinfunction "1_1") (pintype "passive"))
    )
    (net (code "33") (name "/RS485_B2") (class "Default")
      (node (ref "C15") (pin "2") (pinfunction "2_2") (pintype "passive"))
      (node (ref "HD1") (pin "5") (pinfunction "5_5") (pintype "passive"))
      (node (ref "R38") (pin "2") (pinfunction "2_2") (pintype "passive"))
      (node (ref "R44") (pin "2") (pinfunction "2_2") (pintype "passive"))
      (node (ref "R46") (pin "1") (pinfunction "1_1") (pintype "passive"))
    )
    (net (code "34") (name "/RS485_ENB1") (class "Default")
      (node (ref "IC1") (pin "2") (pinfunction "~{RE}_2") (pintype "passive"))
      (node (ref "IC1") (pin "3") (pinfunction "DE_3") (pintype "passive"))
      (node (ref "R22") (pin "2") (pinfunction "2_2") (pintype "passive"))
      (node (ref "R28") (pin "2") (pinfunction "2_2") (pintype "passive"))
    )
    (net (code "35") (name "/RS485_ENB2") (class "Default")
      (node (ref "IC2") (pin "2") (pinfunction "~{RE}_2") (pintype "passive"))
      (node (ref "IC2") (pin "3") (pinfunction "DE_3") (pintype "passive"))
      (node (ref "R41") (pin "2") (pinfunction "2_2") (pintype "passive"))
      (node (ref "R45") (pin "2") (pinfunction "2_2") (pintype "passive"))
    )
    (net (code "36") (name "/RS485_RX1") (class "Default")
      (node (ref "IC1") (pin "4") (pinfunction "DI_4") (pintype "passive"))
      (node (ref "R21") (pin "2") (pinfunction "2_2") (pintype "passive"))
      (node (ref "R31") (pin "2") (pinfunction "2_2") (pintype "passive"))
    )
    (net (code "37") (name "/RS485_RX2") (class "Default")
      (node (ref "IC2") (pin "4") (pinfunction "DI_4") (pintype "passive"))
      (node (ref "R40") (pin "2") (pinfunction "2_2") (pintype "passive"))
      (node (ref "R47") (pin "2") (pinfunction "2_2") (pintype "passive"))
    )
    (net (code "38") (name "/RS485_TX1") (class "Default")
      (node (ref "IC1") (pin "1") (pinfunction "RO_1") (pintype "passive"))
      (node (ref "R23") (pin "2") (pinfunction "2_2") (pintype "passive"))
      (node (ref "R26") (pin "2") (pinfunction "2_2") (pintype "passive"))
    )
    (net (code "39") (name "/RS485_TX2") (class "Default")
      (node (ref "IC2") (pin "1") (pinfunction "RO_1") (pintype "passive"))
      (node (ref "R42") (pin "2") (pinfunction "2_2") (pintype "passive"))
      (node (ref "R43") (pin "2") (pinfunction "2_2") (pintype "passive"))
    )
    (net (code "40") (name "/SPI_CS") (class "Default")
      (node (ref "R63") (pin "1") (pinfunction "1_1") (pintype "passive"))
      (node (ref "U1") (pin "29") (pinfunction "PA4_29") (pintype "bidirectional"))
    )
    (net (code "41") (name "/SPI_INT") (class "Default")
      (node (ref "R72") (pin "1") (pinfunction "1_1") (pintype "passive"))
      (node (ref "U1") (pin "33") (pinfunction "PC4_33") (pintype "bidirectional"))
    )
    (net (code "42") (name "/SPI_MISO") (class "Default")
      (node (ref "R66") (pin "1") (pinfunction "1_1") (pintype "passive"))
      (node (ref "U1") (pin "31") (pinfunction "PA6_31") (pintype "bidirectional"))
    )
    (net (code "43") (name "/SPI_MOSI") (class "Default")
      (node (ref "R68") (pin "1") (pinfunction "1_1") (pintype "passive"))
      (node (ref "U1") (pin "32") (pinfunction "PA7_32") (pintype "bidirectional"))
    )
    (net (code "44") (name "/SPI_SCK") (class "Default")
      (node (ref "R70") (pin "1") (pinfunction "1_1") (pintype "passive"))
      (node (ref "U1") (pin "30") (pinfunction "PA5_30") (pintype "bidirectional"))
    )
    (net (code "45") (name "/SWCLK") (class "Default")
      (node (ref "J1") (pin "2") (pinfunction "2_2") (pintype "passive"))
      (node (ref "U1") (pin "76") (pinfunction "PA14_76") (pintype "bidirectional"))
    )
    (net (code "46") (name "/SW_DIO") (class "Default")
      (node (ref "J1") (pin "4") (pinfunction "4_4") (pintype "passive"))
      (node (ref "U1") (pin "72") (pinfunction "PA13_72") (pintype "bidirectional"))
    )
    (net (code "47") (name "/UART1_ENB") (class "Default")
      (node (ref "R28") (pin "1") (pinfunction "1_1") (pintype "passive"))
      (node (ref "U1") (pin "70") (pinfunction "PA11_70") (pintype "bidirectional"))
    )
    (net (code "48") (name "/UART1_RX") (class "Default")
      (node (ref "R26") (pin "1") (pinfunction "1_1") (pintype "passive"))
      (node (ref "U1") (pin "69") (pinfunction "PA10_69") (pintype "bidirectional"))
    )
    (net (code "49") (name "/UART1_TX") (class "Default")
      (node (ref "R31") (pin "1") (pinfunction "1_1") (pintype "passive"))
      (node (ref "U1") (pin "68") (pinfunction "PA9_68") (pintype "bidirectional"))
    )
    (net (code "50") (name "/UART2_RX") (class "Default")
      (node (ref "R73") (pin "1") (pinfunction "1_1") (pintype "passive"))
      (node (ref "U1") (pin "25") (pinfunction "PA2_25") (pintype "bidirectional"))
    )
    (net (code "51") (name "/UART2_TX") (class "Default")
      (node (ref "R74") (pin "1") (pinfunction "1_1") (pintype "passive"))
      (node (ref "U1") (pin "26") (pinfunction "PA3_26") (pintype "bidirectional"))
    )
    (net (code "52") (name "/UART3_ENB") (class "Default")
      (node (ref "R45") (pin "1") (pinfunction "1_1") (pintype "passive"))
      (node (ref "U1") (pin "57") (pinfunction "PD10_57") (pintype "bidirectional"))
    )
    (net (code "53") (name "/UART3_RX") (class "Default")
      (node (ref "R43") (pin "1") (pinfunction "1_1") (pintype "passive"))
      (node (ref "U1") (pin "56") (pinfunction "PD9_56") (pintype "bidirectional"))
    )
    (net (code "54") (name "/UART3_TX") (class "Default")
      (node (ref "R47") (pin "1") (pinfunction "1_1") (pintype "passive"))
      (node (ref "U1") (pin "55") (pinfunction "PD8_55") (pintype "bidirectional"))
    )
    (net (code "55") (name "/UART4_RX") (class "Default")
      (node (ref "R75") (pin "2") (pinfunction "2_2") (pintype "passive"))
      (node (ref "U1") (pin "79") (pinfunction "PC11_79") (pintype "bidirectional"))
    )
    (net (code "56") (name "/UART4_TX") (class "Default")
      (node (ref "1") (pin "2") (pinfunction "2_2") (pintype "passive"))
      (node (ref "U1") (pin "78") (pinfunction "PC10_78") (pintype "bidirectional"))
    )
    (net (code "57") (name "/UART5_RX") (class "Default")
      (node (ref "R77") (pin "2") (pinfunction "2_2") (pintype "passive"))
      (node (ref "U1") (pin "83") (pinfunction "PD2_83") (pintype "bidirectional"))
    )
    (net (code "58") (name "/UART5_TX") (class "Default")
      (node (ref "R76") (pin "2") (pinfunction "2_2") (pintype "passive"))
      (node (ref "U1") (pin "80") (pinfunction "PC12_80") (pintype "bidirectional"))
    )
    (net (code "59") (name "/USB_N") (class "Default")
      (node (ref "P1") (pin "1") (pinfunction "1_1") (pintype "passive"))
      (node (ref "U3") (pin "26") (pinfunction "IO18_26") (pintype "passive"))
    )
    (net (code "60") (name "/USB_P") (class "Default")
      (node (ref "P1") (pin "2") (pinfunction "2_2") (pintype "passive"))
      (node (ref "U3") (pin "27") (pinfunction "IO19_27") (pintype "passive"))
    )
    (net (code "61") (name "GND") (class "Default")
      (node (ref "BT1") (pin "N") (pinfunction "NEG_N") (pintype "passive"))
      (node (ref "C1") (pin "1") (pinfunction "1_1") (pintype "passive"))
      (node (ref "C10") (pin "2") (pinfunction "2_2") (pintype "passive"))
      (node (ref "C12") (pin "1") (pinfunction "1_1") (pintype "passive"))
      (node (ref "C13") (pin "1") (pinfunction "1_1") (pintype "passive"))
      (node (ref "C14") (pin "1") (pinfunction "1_1") (pintype "passive"))
      (node (ref "C16") (pin "1") (pinfunction "1_1") (pintype "passive"))
      (node (ref "C17") (pin "1") (pinfunction "1_1") (pintype "passive"))
      (node (ref "C18") (pin "1") (pinfunction "1_1") (pintype "passive"))
      (node (ref "C19") (pin "1") (pinfunction "1_1") (pintype "passive"))
      (node (ref "C2") (pin "1") (pinfunction "1_1") (pintype "passive"))
      (node (ref "C20") (pin "1") (pinfunction "1_1") (pintype "passive"))
      (node (ref "C21") (pin "1") (pinfunction "1_1") (pintype "passive"))
      (node (ref "C22") (pin "1") (pinfunction "1_1") (pintype "passive"))
      (node (ref "C23") (pin "1") (pinfunction "1_1") (pintype "passive"))
      (node (ref "C24") (pin "1") (pinfunction "1_1") (pintype "passive"))
      (node (ref "C25") (pin "2") (pinfunction "2_2") (pintype "passive"))
      (node (ref "C26") (pin "1") (pinfunction "1_1") (pintype "passive"))
      (node (ref "C27") (pin "1") (pinfunction "1_1") (pintype "passive"))
      (node (ref "C28") (pin "1") (pinfunction "1_1") (pintype "passive"))
      (node (ref "C3") (pin "1") (pinfunction "1_1") (pintype "passive"))
      (node (ref "C4") (pin "1") (pinfunction "1_1") (pintype "passive"))
      (node (ref "C5") (pin "2") (pinfunction "2_2") (pintype "passive"))
      (node (ref "C6") (pin "1") (pinfunction "1_1") (pintype "passive"))
      (node (ref "C7") (pin "1") (pinfunction "1_1") (pintype "passive"))
      (node (ref "C8") (pin "1") (pinfunction "1_1") (pintype "passive"))
      (node (ref "C9") (pin "1") (pinfunction "1_1") (pintype "passive"))
      (node (ref "HD1") (pin "8") (pinfunction "8_8") (pintype "passive"))
      (node (ref "HD2") (pin "1") (pinfunction "1_1") (pintype "passive"))
      (node (ref "IC1") (pin "5") (pinfunction "GND_5") (pintype "passive"))
      (node (ref "IC2") (pin "5") (pinfunction "GND_5") (pintype "passive"))
      (node (ref "IC3") (pin "9") (pinfunction "VSS_9") (pintype "power_in"))
      (node (ref "J1") (pin "5") (pinfunction "5_5") (pintype "passive"))
      (node (ref "J1") (pin "6") (pinfunction "6_6") (pintype "passive"))
      (node (ref "J2") (pin "7") (pinfunction "GND_7") (pintype "passive"))
      (node (ref "J2") (pin "8") (pinfunction "GND_8") (pintype "passive"))
      (node (ref "LCD1") (pin "1") (pinfunction "VSS_1") (pintype "passive"))
      (node (ref "LED1") (pin "2") (pinfunction "2_2") (pintype "passive"))
      (node (ref "LED2") (pin "2") (pinfunction "2_2") (pintype "passive"))
      (node (ref "LED3") (pin "2") (pinfunction "2_2") (pintype "passive"))
      (node (ref "P1") (pin "4") (pinfunction "4_4") (pintype "passive"))
      (node (ref "Q3") (pin "2") (pinfunction "E_2") (pintype "passive"))
      (node (ref "Q8") (pin "2") (pinfunction "E_2") (pintype "passive"))
      (node (ref "Q9") (pin "2") (pinfunction "E_2") (pintype "passive"))
      (node (ref "R20") (pin "1") (pinfunction "1_1") (pintype "passive"))
      (node (ref "R38") (pin "1") (pinfunction "1_1") (pintype "passive"))
      (node (ref "R8") (pin "1") (pinfunction "1_1") (pintype "passive"))
      (node (ref "SW1") (pin "1") (pintype "passive"))
      (node (ref "SW2") (pin "1") (pinfunction "1_1") (pintype "passive"))
      (node (ref "SW3") (pin "1") (pinfunction "1_1") (pintype "passive"))
      (node (ref "SW4") (pin "1") (pinfunction "1_1") (pintype "passive"))
      (node (ref "U1") (pin "10") (pinfunction "VSS_5_10") (pintype "power_in"))
      (node (ref "U1") (pin "27") (pinfunction "VSS_4_27") (pintype "power_in"))
      (node (ref "U1") (pin "49") (pinfunction "VSS_1_49") (pintype "power_in"))
      (node (ref "U1") (pin "74") (pinfunction "VSS_2_74") (pintype "power_in"))
      (node (ref "U1") (pin "99") (pinfunction "VSS_3_99") (pintype "power_in"))
      (node (ref "U2") (pin "1") (pinfunction "A0_1") (pintype "passive"))
      (node (ref "U2") (pin "2") (pinfunction "A1_2") (pintype "passive"))
      (node (ref "U2") (pin "3") (pinfunction "A2_3") (pintype "passive"))
      (node (ref "U2") (pin "4") (pinfunction "GND_4") (pintype "power_in"))
      (node (ref "U2") (pin "7") (pinfunction "WP_7") (pintype "passive"))
      (node (ref "U3") (pin "1") (pinfunction "GND_1") (pintype "power_in"))
      (node (ref "U3") (pin "11") (pinfunction "GND_11") (pintype "power_in"))
      (node (ref "U3") (pin "14") (pinfunction "GND_14") (pintype "power_in"))
      (node (ref "U3") (pin "2") (pinfunction "GND_2") (pintype "power_in"))
      (node (ref "U3") (pin "36") (pinfunction "GND_36") (pintype "power_in"))
      (node (ref "U3") (pin "37") (pinfunction "GND_37") (pintype "power_in"))
      (node (ref "U3") (pin "38") (pinfunction "GND_38") (pintype "power_in"))
      (node (ref "U3") (pin "39") (pinfunction "GND_39") (pintype "power_in"))
      (node (ref "U3") (pin "40") (pinfunction "GND_40") (pintype "power_in"))
      (node (ref "U3") (pin "41") (pinfunction "GND_41") (pintype "power_in"))
      (node (ref "U3") (pin "42") (pinfunction "GND_42") (pintype "power_in"))
      (node (ref "U3") (pin "43") (pinfunction "GND_43") (pintype "power_in"))
      (node (ref "U3") (pin "44") (pinfunction "GND_44") (pintype "power_in"))
      (node (ref "U3") (pin "45") (pinfunction "GND_45") (pintype "power_in"))
      (node (ref "U3") (pin "46") (pinfunction "GND_46") (pintype "power_in"))
      (node (ref "U3") (pin "47") (pinfunction "GND_47") (pintype "power_in"))
      (node (ref "U3") (pin "48") (pinfunction "GND_48") (pintype "power_in"))
      (node (ref "U3") (pin "49_1") (pinfunction "GND_49_1") (pintype "power_in"))
      (node (ref "U3") (pin "49_2") (pinfunction "GND_49_2") (pintype "power_in"))
      (node (ref "U3") (pin "49_3") (pinfunction "GND_49_3") (pintype "power_in"))
      (node (ref "U3") (pin "49_4") (pinfunction "GND_49_4") (pintype "power_in"))
      (node (ref "U3") (pin "49_5") (pinfunction "GND_49_5") (pintype "power_in"))
      (node (ref "U3") (pin "49_6") (pinfunction "GND_49_6") (pintype "power_in"))
      (node (ref "U3") (pin "49_7") (pinfunction "GND_49_7") (pintype "power_in"))
      (node (ref "U3") (pin "49_8") (pinfunction "GND_49_8") (pintype "power_in"))
      (node (ref "U3") (pin "49_9") (pinfunction "GND_49_9") (pintype "power_in"))
      (node (ref "U3") (pin "50") (pinfunction "GND_50") (pintype "power_in"))
      (node (ref "U3") (pin "51") (pinfunction "GND_51") (pintype "power_in"))
      (node (ref "U3") (pin "52") (pinfunction "GND_52") (pintype "power_in"))
      (node (ref "U3") (pin "53") (pinfunction "GND_53") (pintype "power_in"))
      (node (ref "U4") (pin "2") (pinfunction "GND_2") (pintype "passive"))
      (node (ref "U4") (pin "8") (pinfunction "S_8") (pintype "passive"))
      (node (ref "VZ1") (pin "1") (pinfunction "1_1") (pintype "passive"))
      (node (ref "X1") (pin "2") (pinfunction "GND_2") (pintype "power_in"))
      (node (ref "X1") (pin "4") (pinfunction "GND_4") (pintype "power_in"))
      (node (ref "X3") (pin "2") (pinfunction "GND_2") (pintype "power_in"))
      (node (ref "X3") (pin "4") (pinfunction "GND_4") (pintype "power_in"))
    )
    (net (code "62") (name "Net-(1-Pad1)") (class "Default")
      (node (ref "1") (pin "1") (pinfunction "1_1") (pintype "passive"))
      (node (ref "HD2") (pin "2") (pinfunction "2_2") (pintype "passive"))
    )
    (net (code "63") (name "Net-(BT1-POS)") (class "Default")
      (node (ref "BT1") (pin "P") (pinfunction "POS_P") (pintype "passive"))
      (node (ref "C2") (pin "2") (pinfunction "2_2") (pintype "passive"))
      (node (ref "U1") (pin "6") (pinfunction "VBAT_6") (pintype "power_in"))
    )
    (net (code "64") (name "Net-(HD2-Pad3)") (class "Default")
      (node (ref "HD2") (pin "3") (pinfunction "3_3") (pintype "passive"))
      (node (ref "R75") (pin "1") (pinfunction "1_1") (pintype "passive"))
    )
    (net (code "65") (name "Net-(IC1-A)") (class "Default")
      (node (ref "IC1") (pin "6") (pinfunction "A_6") (pintype "passive"))
      (node (ref "R32") (pin "1") (pinfunction "1_1") (pintype "passive"))
    )
    (net (code "66") (name "Net-(IC1-B)") (class "Default")
      (node (ref "IC1") (pin "7") (pinfunction "B_7") (pintype "passive"))
      (node (ref "R27") (pin "1") (pinfunction "1_1") (pintype "passive"))
    )
    (net (code "67") (name "Net-(IC2-A)") (class "Default")
      (node (ref "IC2") (pin "6") (pinfunction "A_6") (pintype "passive"))
      (node (ref "R48") (pin "1") (pinfunction "1_1") (pintype "passive"))
    )
    (net (code "68") (name "Net-(IC2-B)") (class "Default")
      (node (ref "IC2") (pin "7") (pinfunction "B_7") (pintype "passive"))
      (node (ref "R44") (pin "1") (pinfunction "1_1") (pintype "passive"))
    )
    (net (code "69") (name "Net-(IC3-OSC1)") (class "Default")
      (node (ref "C27") (pin "2") (pinfunction "2_2") (pintype "passive"))
      (node (ref "IC3") (pin "8") (pinfunction "OSC1_8") (pintype "input"))
      (node (ref "X3") (pin "3") (pinfunction "XTAL_3") (pintype "passive"))
    )
    (net (code "70") (name "Net-(IC3-OSC2)") (class "Default")
      (node (ref "C26") (pin "2") (pinfunction "2_2") (pintype "passive"))
      (node (ref "IC3") (pin "7") (pinfunction "OSC2_7") (pintype "output"))
      (node (ref "X3") (pin "1") (pinfunction "XTAL_1") (pintype "passive"))
    )
    (net (code "71") (name "Net-(IC3-RXCAN)") (class "Default")
      (node (ref "IC3") (pin "2") (pinfunction "RXCAN_2") (pintype "input"))
      (node (ref "U4") (pin "4") (pinfunction "RXD_4") (pintype "passive"))
    )
    (net (code "72") (name "Net-(IC3-SCK)") (class "Default")
      (node (ref "IC3") (pin "13") (pinfunction "SCK_13") (pintype "passive"))
      (node (ref "R70") (pin "2") (pinfunction "2_2") (pintype "passive"))
    )
    (net (code "73") (name "Net-(IC3-SI)") (class "Default")
      (node (ref "IC3") (pin "14") (pinfunction "SI_14") (pintype "passive"))
      (node (ref "R68") (pin "2") (pinfunction "2_2") (pintype "passive"))
    )
    (net (code "74") (name "Net-(IC3-SO)") (class "Default")
      (node (ref "IC3") (pin "15") (pinfunction "SO_15") (pintype "passive"))
      (node (ref "R66") (pin "2") (pinfunction "2_2") (pintype "passive"))
    )
    (net (code "75") (name "Net-(IC3-TXCAN)") (class "Default")
      (node (ref "IC3") (pin "1") (pinfunction "TXCAN_1") (pintype "output"))
      (node (ref "U4") (pin "1") (pinfunction "TXD_1") (pintype "passive"))
    )
    (net (code "76") (name "Net-(IC3-~{CS})") (class "Default")
      (node (ref "IC3") (pin "16") (pinfunction "~{CS}_16") (pintype "passive"))
      (node (ref "R63") (pin "2") (pinfunction "2_2") (pintype "passive"))
    )
    (net (code "77") (name "Net-(IC3-~{INT})") (class "Default")
      (node (ref "IC3") (pin "12") (pinfunction "~{INT}_12") (pintype "passive"))
      (node (ref "R72") (pin "2") (pinfunction "2_2") (pintype "passive"))
    )
    (net (code "78") (name "Net-(IC3-~{RESET})") (class "Default")
      (node (ref "C24") (pin "2") (pinfunction "2_2") (pintype "passive"))
      (node (ref "IC3") (pin "17") (pinfunction "~{RESET}_17") (pintype "passive"))
      (node (ref "R59") (pin "2") (pinfunction "2_2") (pintype "passive"))
    )
    (net (code "79") (name "Net-(J2-RX2)") (class "Default")
      (node (ref "J2") (pin "5") (pinfunction "RX2_5") (pintype "passive"))
      (node (ref "R74") (pin "2") (pinfunction "2_2") (pintype "passive"))
    )
    (net (code "80") (name "Net-(J2-TX2)") (class "Default")
      (node (ref "J2") (pin "4") (pinfunction "TX2_4") (pintype "passive"))
      (node (ref "R73") (pin "2") (pinfunction "2_2") (pintype "passive"))
    )
    (net (code "81") (name "Net-(LCD1-A)") (class "Default")
      (node (ref "LCD1") (pin "19") (pinfunction "A_19") (pintype "passive"))
      (node (ref "R65") (pin "2") (pinfunction "2_2") (pintype "passive"))
    )
    (net (code "82") (name "Net-(LCD1-D4)") (class "Default")
      (node (ref "LCD1") (pin "11") (pinfunction "D4_11") (pintype "passive"))
      (node (ref "R53") (pin "2") (pinfunction "2_2") (pintype "passive"))
    )
    (net (code "83") (name "Net-(LCD1-D5)") (class "Default")
      (node (ref "LCD1") (pin "12") (pinfunction "D5_12") (pintype "passive"))
      (node (ref "R54") (pin "2") (pinfunction "2_2") (pintype "passive"))
    )
    (net (code "84") (name "Net-(LCD1-D6)") (class "Default")
      (node (ref "LCD1") (pin "13") (pinfunction "D6_13") (pintype "passive"))
      (node (ref "R55") (pin "2") (pinfunction "2_2") (pintype "passive"))
    )
    (net (code "85") (name "Net-(LCD1-D7)") (class "Default")
      (node (ref "LCD1") (pin "14") (pinfunction "D7_14") (pintype "passive"))
      (node (ref "R56") (pin "2") (pinfunction "2_2") (pintype "passive"))
    )
    (net (code "86") (name "Net-(LCD1-K)") (class "Default")
      (node (ref "LCD1") (pin "20") (pinfunction "K_20") (pintype "passive"))
      (node (ref "Q9") (pin "3") (pinfunction "C_3") (pintype "passive"))
    )
    (net (code "87") (name "Net-(LCD1-PSB)") (class "Default")
      (node (ref "LCD1") (pin "15") (pinfunction "PSB_15") (pintype "passive"))
      (node (ref "R57") (pin "2") (pinfunction "2_2") (pintype "passive"))
    )
    (net (code "88") (name "Net-(LCD1-RS)") (class "Default")
      (node (ref "LCD1") (pin "4") (pinfunction "RS_4") (pintype "passive"))
      (node (ref "R60") (pin "2") (pinfunction "2_2") (pintype "passive"))
    )
    (net (code "89") (name "Net-(LCD1-R{slash}~{W})") (class "Default")
      (node (ref "LCD1") (pin "5") (pinfunction "R/~{W}_5") (pintype "passive"))
      (node (ref "R61") (pin "2") (pinfunction "2_2") (pintype "passive"))
    )
    (net (code "90") (name "Net-(LCD1-V0)") (class "Default")
      (node (ref "C28") (pin "2") (pinfunction "2_2") (pintype "passive"))
      (node (ref "LCD1") (pin "3") (pinfunction "V0_3") (pintype "passive"))
      (node (ref "R67") (pin "2") (pinfunction "2_2") (pintype "passive"))
    )
    (net (code "91") (name "Net-(LCD1-~{EN})") (class "Default")
      (node (ref "LCD1") (pin "6") (pinfunction "~{EN}_6") (pintype "passive"))
      (node (ref "R62") (pin "2") (pinfunction "2_2") (pintype "passive"))
    )
    (net (code "92") (name "Net-(LCD1-~{RES})") (class "Default")
      (node (ref "LCD1") (pin "17") (pinfunction "~{RES}_17") (pintype "passive"))
      (node (ref "R58") (pin "2") (pinfunction "2_2") (pintype "passive"))
    )
    (net (code "93") (name "Net-(LED1-Pad1)") (class "Default")
      (node (ref "LED1") (pin "1") (pinfunction "1_1") (pintype "passive"))
      (node (ref "R6") (pin "2") (pinfunction "2_2") (pintype "passive"))
    )
    (net (code "94") (name "Net-(LED1-Pad3)") (class "Default")
      (node (ref "LED1") (pin "3") (pinfunction "3_3") (pintype "passive"))
      (node (ref "R3") (pin "2") (pinfunction "2_2") (pintype "passive"))
    )
    (net (code "95") (name "Net-(LED2-Pad1)") (class "Default")
      (node (ref "LED2") (pin "1") (pinfunction "1_1") (pintype "passive"))
      (node (ref "R16") (pin "2") (pinfunction "2_2") (pintype "passive"))
    )
    (net (code "96") (name "Net-(LED2-Pad3)") (class "Default")
      (node (ref "LED2") (pin "3") (pinfunction "3_3") (pintype "passive"))
      (node (ref "R15") (pin "2") (pinfunction "2_2") (pintype "passive"))
    )
    (net (code "97") (name "Net-(LED3-Pad1)") (class "Default")
      (node (ref "LED3") (pin "1") (pinfunction "1_1") (pintype "passive"))
      (node (ref "R33") (pin "2") (pinfunction "2_2") (pintype "passive"))
    )
    (net (code "98") (name "Net-(LED3-Pad3)") (class "Default")
      (node (ref "LED3") (pin "3") (pinfunction "3_3") (pintype "passive"))
      (node (ref "R30") (pin "2") (pinfunction "2_2") (pintype "passive"))
    )
    (net (code "99") (name "Net-(Q1-B)") (class "Default")
      (node (ref "Q1") (pin "3") (pinfunction "B_3") (pintype "passive"))
      (node (ref "R1") (pin "1") (pinfunction "1_1") (pintype "passive"))
      (node (ref "R2") (pin "1") (pinfunction "1_1") (pintype "passive"))
    )
    (net (code "100") (name "Net-(Q1-C)") (class "Default")
      (node (ref "Q1") (pin "2") (pinfunction "C_2") (pintype "passive"))
      (node (ref "R3") (pin "1") (pinfunction "1_1") (pintype "passive"))
    )
    (net (code "101") (name "Net-(Q2-B)") (class "Default")
      (node (ref "Q2") (pin "3") (pinfunction "B_3") (pintype "passive"))
      (node (ref "R10") (pin "1") (pinfunction "1_1") (pintype "passive"))
      (node (ref "R9") (pin "1") (pinfunction "1_1") (pintype "passive"))
    )
    (net (code "102") (name "Net-(Q2-C)") (class "Default")
      (node (ref "Q2") (pin "2") (pinfunction "C_2") (pintype "passive"))
      (node (ref "R6") (pin "1") (pinfunction "1_1") (pintype "passive"))
    )
    (net (code "103") (name "Net-(Q3-B)") (class "Default")
      (node (ref "Q3") (pin "1") (pinfunction "B_1") (pintype "passive"))
      (node (ref "R11") (pin "2") (pinfunction "2_2") (pintype "passive"))
    )
    (net (code "104") (name "Net-(Q3-C)") (class "Default")
      (node (ref "LS1") (pin "2") (pinfunction "2_2") (pintype "passive"))
      (node (ref "Q3") (pin "3") (pinfunction "C_3") (pintype "passive"))
    )
    (net (code "105") (name "Net-(Q4-B)") (class "Default")
      (node (ref "Q4") (pin "3") (pinfunction "B_3") (pintype "passive"))
      (node (ref "R13") (pin "1") (pinfunction "1_1") (pintype "passive"))
      (node (ref "R14") (pin "1") (pinfunction "1_1") (pintype "passive"))
    )
    (net (code "106") (name "Net-(Q4-C)") (class "Default")
      (node (ref "Q4") (pin "2") (pinfunction "C_2") (pintype "passive"))
      (node (ref "R15") (pin "1") (pinfunction "1_1") (pintype "passive"))
    )
    (net (code "107") (name "Net-(Q5-B)") (class "Default")
      (node (ref "Q5") (pin "3") (pinfunction "B_3") (pintype "passive"))
      (node (ref "R17") (pin "1") (pinfunction "1_1") (pintype "passive"))
      (node (ref "R18") (pin "1") (pinfunction "1_1") (pintype "passive"))
    )
    (net (code "108") (name "Net-(Q5-C)") (class "Default")
      (node (ref "Q5") (pin "2") (pinfunction "C_2") (pintype "passive"))
      (node (ref "R16") (pin "1") (pinfunction "1_1") (pintype "passive"))
    )
    (net (code "109") (name "Net-(Q6-B)") (class "Default")
      (node (ref "Q6") (pin "3") (pinfunction "B_3") (pintype "passive"))
      (node (ref "R24") (pin "1") (pinfunction "1_1") (pintype "passive"))
      (node (ref "R25") (pin "1") (pinfunction "1_1") (pintype "passive"))
    )
    (net (code "110") (name "Net-(Q6-C)") (class "Default")
      (node (ref "Q6") (pin "2") (pinfunction "C_2") (pintype "passive"))
      (node (ref "R30") (pin "1") (pinfunction "1_1") (pintype "passive"))
    )
    (net (code "111") (name "Net-(Q7-B)") (class "Default")
      (node (ref "Q7") (pin "3") (pinfunction "B_3") (pintype "passive"))
      (node (ref "R35") (pin "1") (pinfunction "1_1") (pintype "passive"))
      (node (ref "R36") (pin "1") (pinfunction "1_1") (pintype "passive"))
    )
    (net (code "112") (name "Net-(Q7-C)") (class "Default")
      (node (ref "Q7") (pin "2") (pinfunction "C_2") (pintype "passive"))
      (node (ref "R33") (pin "1") (pinfunction "1_1") (pintype "passive"))
    )
    (net (code "113") (name "Net-(Q8-B)") (class "Default")
      (node (ref "Q8") (pin "1") (pinfunction "B_1") (pintype "passive"))
      (node (ref "R69") (pin "2") (pinfunction "2_2") (pintype "passive"))
    )
    (net (code "114") (name "Net-(Q8-C)") (class "Default")
      (node (ref "Q8") (pin "3") (pinfunction "C_3") (pintype "passive"))
      (node (ref "R64") (pin "2") (pinfunction "2_2") (pintype "passive"))
      (node (ref "R67") (pin "1") (pinfunction "1_1") (pintype "passive"))
    )
    (net (code "115") (name "Net-(Q9-B)") (class "Default")
      (node (ref "Q9") (pin "1") (pinfunction "B_1") (pintype "passive"))
      (node (ref "R71") (pin "2") (pinfunction "2_2") (pintype "passive"))
    )
    (net (code "116") (name "Net-(U1-BOOT0)") (class "Default")
      (node (ref "R8") (pin "2") (pinfunction "2_2") (pintype "passive"))
      (node (ref "U1") (pin "94") (pinfunction "BOOT0_94") (pintype "input"))
    )
    (net (code "117") (name "Net-(U1-NRST)") (class "Default")
      (node (ref "C5") (pin "1") (pinfunction "1_1") (pintype "passive"))
      (node (ref "R7") (pin "2") (pinfunction "2_2") (pintype "passive"))
      (node (ref "U1") (pin "14") (pinfunction "NRST_14") (pintype "bidirectional"))
    )
    (net (code "118") (name "Net-(U1-OSC_IN)") (class "Default")
      (node (ref "C4") (pin "2") (pinfunction "2_2") (pintype "passive"))
      (node (ref "R12") (pin "1") (pinfunction "1_1") (pintype "passive"))
      (node (ref "U1") (pin "12") (pinfunction "OSC_IN_12") (pintype "input"))
      (node (ref "X1") (pin "3") (pinfunction "XTAL_3") (pintype "passive"))
    )
    (net (code "119") (name "Net-(U1-OSC_OUT)") (class "Default")
      (node (ref "C3") (pin "2") (pinfunction "2_2") (pintype "passive"))
      (node (ref "R12") (pin "2") (pinfunction "2_2") (pintype "passive"))
      (node (ref "U1") (pin "13") (pinfunction "OSC_OUT_13") (pintype "output"))
      (node (ref "X1") (pin "1") (pinfunction "XTAL_1") (pintype "passive"))
    )
    (net (code "120") (name "Net-(U1-PC14{slash}OSC32_IN)") (class "Default")
      (node (ref "C17") (pin "2") (pinfunction "2_2") (pintype "passive"))
      (node (ref "U1") (pin "8") (pinfunction "PC14/OSC32_IN_8") (pintype "bidirectional"))
      (node (ref "X2") (pin "2") (pinfunction "2_2") (pintype "passive"))
    )
    (net (code "121") (name "Net-(U1-PC15-OSC32_OUT)") (class "Default")
      (node (ref "C18") (pin "2") (pinfunction "2_2") (pintype "passive"))
      (node (ref "U1") (pin "9") (pinfunction "PC15-OSC32_OUT_9") (pintype "bidirectional"))
      (node (ref "X2") (pin "1") (pinfunction "1_1") (pintype "passive"))
    )
    (net (code "122") (name "Net-(VZ1-Pad2)") (class "Default")
      (node (ref "VZ1") (pin "2") (pinfunction "2_2") (pintype "passive"))
      (node (ref "via1") (pin "1") (pinfunction "1_1") (pintype "passive"))
      (node (ref "via2") (pin "1") (pinfunction "1_1") (pintype "passive"))
      (node (ref "via3") (pin "1") (pinfunction "1_1") (pintype "passive"))
      (node (ref "via4") (pin "1") (pinfunction "1_1") (pintype "passive"))
    )
    (net (code "123") (name "VCC_5V") (class "Default")
      (node (ref "C12") (pin "2") (pinfunction "2_2") (pintype "passive"))
      (node (ref "C14") (pin "2") (pinfunction "2_2") (pintype "passive"))
      (node (ref "C21") (pin "2") (pinfunction "2_2") (pintype "passive"))
      (node (ref "C22") (pin "2") (pinfunction "2_2") (pintype "passive"))
      (node (ref "C23") (pin "2") (pinfunction "2_2") (pintype "passive"))
      (node (ref "C25") (pin "1") (pinfunction "1_1") (pintype "passive"))
      (node (ref "C8") (pin "2") (pinfunction "2_2") (pintype "passive"))
      (node (ref "C9") (pin "2") (pinfunction "2_2") (pintype "passive"))
      (node (ref "HD2") (pin "4") (pinfunction "4_4") (pintype "passive"))
      (node (ref "IC1") (pin "8") (pinfunction "VCC_8") (pintype "passive"))
      (node (ref "IC2") (pin "8") (pinfunction "VCC_8") (pintype "passive"))
      (node (ref "IC3") (pin "18") (pinfunction "VDD_18") (pintype "power_in"))
      (node (ref "J1") (pin "10") (pinfunction "10_10") (pintype "passive"))
      (node (ref "J1") (pin "9") (pinfunction "9_9") (pintype "passive"))
      (node (ref "LCD1") (pin "2") (pinfunction "VDD_2") (pintype "passive"))
      (node (ref "LS1") (pin "1") (pinfunction "1_1") (pintype "passive"))
      (node (ref "Q1") (pin "1") (pinfunction "E_1") (pintype "passive"))
      (node (ref "Q2") (pin "1") (pinfunction "E_1") (pintype "passive"))
      (node (ref "Q4") (pin "1") (pinfunction "E_1") (pintype "passive"))
      (node (ref "Q5") (pin "1") (pinfunction "E_1") (pintype "passive"))
      (node (ref "Q6") (pin "1") (pinfunction "E_1") (pintype "passive"))
      (node (ref "Q7") (pin "1") (pinfunction "E_1") (pintype "passive"))
      (node (ref "R1") (pin "2") (pinfunction "2_2") (pintype "passive"))
      (node (ref "R13") (pin "2") (pinfunction "2_2") (pintype "passive"))
      (node (ref "R17") (pin "2") (pinfunction "2_2") (pintype "passive"))
      (node (ref "R21") (pin "1") (pinfunction "1_1") (pintype "passive"))
      (node (ref "R22") (pin "1") (pinfunction "1_1") (pintype "passive"))
      (node (ref "R23") (pin "1") (pinfunction "1_1") (pintype "passive"))
      (node (ref "R24") (pin "2") (pinfunction "2_2") (pintype "passive"))
      (node (ref "R34") (pin "2") (pinfunction "2_2") (pintype "passive"))
      (node (ref "R35") (pin "2") (pinfunction "2_2") (pintype "passive"))
      (node (ref "R40") (pin "1") (pinfunction "1_1") (pintype "passive"))
      (node (ref "R41") (pin "1") (pinfunction "1_1") (pintype "passive"))
      (node (ref "R42") (pin "1") (pinfunction "1_1") (pintype "passive"))
      (node (ref "R50") (pin "2") (pinfunction "2_2") (pintype "passive"))
      (node (ref "R59") (pin "1") (pinfunction "1_1") (pintype "passive"))
      (node (ref "R64") (pin "1") (pinfunction "1_1") (pintype "passive"))
      (node (ref "R65") (pin "1") (pinfunction "1_1") (pintype "passive"))
      (node (ref "R9") (pin "2") (pinfunction "2_2") (pintype "passive"))
      (node (ref "U4") (pin "3") (pinfunction "VCC_3") (pintype "passive"))
    )
    (net (code "124") (name "VDDA_3.3V") (class "Default")
      (node (ref "U1") (pin "21") (pinfunction "VREF+_21") (pintype "power_in"))
      (node (ref "U1") (pin "22") (pinfunction "VDDA_22") (pintype "power_in"))
    )
    (net (code "125") (name "VDD_3.3V") (class "Default")
      (node (ref "C1") (pin "2") (pinfunction "2_2") (pintype "passive"))
      (node (ref "C6") (pin "2") (pinfunction "2_2") (pintype "passive"))
      (node (ref "C7") (pin "2") (pinfunction "2_2") (pintype "passive"))
      (node (ref "J1") (pin "7") (pinfunction "7_7") (pintype "passive"))
      (node (ref "J1") (pin "8") (pinfunction "8_8") (pintype "passive"))
      (node (ref "R19") (pin "1") (pinfunction "1_1") (pintype "passive"))
      (node (ref "R37") (pin "2") (pinfunction "2_2") (pintype "passive"))
      (node (ref "R39") (pin "2") (pinfunction "2_2") (pintype "passive"))
      (node (ref "R4") (pin "1") (pinfunction "1_1") (pintype "passive"))
      (node (ref "R49") (pin "2") (pinfunction "2_2") (pintype "passive"))
      (node (ref "R5") (pin "1") (pinfunction "1_1") (pintype "passive"))
      (node (ref "R51") (pin "2") (pinfunction "2_2") (pintype "passive"))
      (node (ref "R7") (pin "1") (pinfunction "1_1") (pintype "passive"))
      (node (ref "U1") (pin "100") (pinfunction "VDD_3_100") (pintype "power_in"))
      (node (ref "U1") (pin "11") (pinfunction "VDD_5_11") (pintype "power_in"))
      (node (ref "U1") (pin "28") (pinfunction "VDD_4_28") (pintype "power_in"))
      (node (ref "U1") (pin "50") (pinfunction "VDD_1_50") (pintype "power_in"))
      (node (ref "U1") (pin "75") (pinfunction "VDD_2_75") (pintype "power_in"))
      (node (ref "U2") (pin "8") (pinfunction "VCC_8") (pintype "power_in"))
      (node (ref "U3") (pin "3") (pinfunction "3V3_3") (pintype "power_in"))
    )
    (net (code "126") (name "VIN") (class "Default")
      (node (ref "HD1") (pin "10") (pinfunction "10_10") (pintype "passive"))
      (node (ref "J2") (pin "1") (pinfunction "VCC_(6-36V)_1") (pintype "passive"))
      (node (ref "J2") (pin "2") (pinfunction "VCC_2") (pintype "passive"))
    )
    (net (code "127") (name "VSSA") (class "Default")
      (node (ref "U1") (pin "19") (pinfunction "VSSA_19") (pintype "power_in"))
      (node (ref "U1") (pin "20") (pinfunction "VREF-_20") (pintype "power_in"))
    )
    (net (code "128") (name "unconnected-(HD1-Pad4)") (class "Default")
      (node (ref "HD1") (pin "4") (pinfunction "4_4") (pintype "passive"))
    )
    (net (code "129") (name "unconnected-(HD1-Pad6)") (class "Default")
      (node (ref "HD1") (pin "6") (pinfunction "6_6") (pintype "passive"))
    )
    (net (code "130") (name "unconnected-(IC3-CLKOUT{slash}SOF-Pad3)") (class "Default")
      (node (ref "IC3") (pin "3") (pinfunction "CLKOUT/SOF_3") (pintype "output"))
    )
    (net (code "131") (name "unconnected-(IC3-~{RX0BF}-Pad11)") (class "Default")
      (node (ref "IC3") (pin "11") (pinfunction "~{RX0BF}_11") (pintype "output"))
    )
    (net (code "132") (name "unconnected-(IC3-~{RX1BF}-Pad10)") (class "Default")
      (node (ref "IC3") (pin "10") (pinfunction "~{RX1BF}_10") (pintype "output"))
    )
    (net (code "133") (name "unconnected-(IC3-~{TX0RTS}-Pad4)") (class "Default")
      (node (ref "IC3") (pin "4") (pinfunction "~{TX0RTS}_4") (pintype "passive"))
    )
    (net (code "134") (name "unconnected-(IC3-~{TX1RTS}-Pad5)") (class "Default")
      (node (ref "IC3") (pin "5") (pinfunction "~{TX1RTS}_5") (pintype "passive"))
    )
    (net (code "135") (name "unconnected-(IC3-~{TX2RTS}-Pad6)") (class "Default")
      (node (ref "IC3") (pin "6") (pinfunction "~{TX2RTS}_6") (pintype "passive"))
    )
    (net (code "136") (name "unconnected-(J1-Pad1)") (class "Default")
      (node (ref "J1") (pin "1") (pinfunction "1_1") (pintype "passive"))
    )
    (net (code "137") (name "unconnected-(J1-Pad3)") (class "Default")
      (node (ref "J1") (pin "3") (pinfunction "3_3") (pintype "passive"))
    )
    (net (code "138") (name "unconnected-(J2-RX4-Pad6)") (class "Default")
      (node (ref "J2") (pin "6") (pinfunction "RX4_6") (pintype "passive"))
    )
    (net (code "139") (name "unconnected-(J2-TX4-Pad3)") (class "Default")
      (node (ref "J2") (pin "3") (pinfunction "TX4_3") (pintype "passive"))
    )
    (net (code "140") (name "unconnected-(LCD1-D0-Pad7)") (class "Default")
      (node (ref "LCD1") (pin "7") (pinfunction "D0_7") (pintype "passive"))
    )
    (net (code "141") (name "unconnected-(LCD1-D1-Pad8)") (class "Default")
      (node (ref "LCD1") (pin "8") (pinfunction "D1_8") (pintype "passive"))
    )
    (net (code "142") (name "unconnected-(LCD1-D2-Pad9)") (class "Default")
      (node (ref "LCD1") (pin "9") (pinfunction "D2_9") (pintype "passive"))
    )
    (net (code "143") (name "unconnected-(LCD1-D3-Pad10)") (class "Default")
      (node (ref "LCD1") (pin "10") (pinfunction "D3_10") (pintype "passive"))
    )
    (net (code "144") (name "unconnected-(LCD1-NC-Pad16)") (class "Default")
      (node (ref "LCD1") (pin "16") (pinfunction "NC_16") (pintype "passive"))
    )
    (net (code "145") (name "unconnected-(LCD1-VEE-Pad18)") (class "Default")
      (node (ref "LCD1") (pin "18") (pinfunction "VEE_18") (pintype "passive"))
    )
    (net (code "146") (name "unconnected-(U1-PA1-Pad24)") (class "Default")
      (node (ref "U1") (pin "24") (pinfunction "PA1_24") (pintype "bidirectional"))
    )
    (net (code "147") (name "unconnected-(U1-PA8-Pad67)") (class "Default")
      (node (ref "U1") (pin "67") (pinfunction "PA8_67") (pintype "bidirectional"))
    )
    (net (code "148") (name "unconnected-(U1-PA12-Pad71)") (class "Default")
      (node (ref "U1") (pin "71") (pinfunction "PA12_71") (pintype "bidirectional"))
    )
    (net (code "149") (name "unconnected-(U1-PA15-Pad77)") (class "Default")
      (node (ref "U1") (pin "77") (pinfunction "PA15_77") (pintype "bidirectional"))
    )
    (net (code "150") (name "unconnected-(U1-PB0-Pad35)") (class "Default")
      (node (ref "U1") (pin "35") (pinfunction "PB0_35") (pintype "bidirectional"))
    )
    (net (code "151") (name "unconnected-(U1-PB1-Pad36)") (class "Default")
      (node (ref "U1") (pin "36") (pinfunction "PB1_36") (pintype "bidirectional"))
    )
    (net (code "152") (name "unconnected-(U1-PB2-Pad37)") (class "Default")
      (node (ref "U1") (pin "37") (pinfunction "PB2_37") (pintype "bidirectional"))
    )
    (net (code "153") (name "unconnected-(U1-PB7-Pad93)") (class "Default")
      (node (ref "U1") (pin "93") (pinfunction "PB7_93") (pintype "bidirectional"))
    )
    (net (code "154") (name "unconnected-(U1-PB10-Pad47)") (class "Default")
      (node (ref "U1") (pin "47") (pinfunction "PB10_47") (pintype "bidirectional"))
    )
    (net (code "155") (name "unconnected-(U1-PB11-Pad48)") (class "Default")
      (node (ref "U1") (pin "48") (pinfunction "PB11_48") (pintype "bidirectional"))
    )
    (net (code "156") (name "unconnected-(U1-PB12-Pad51)") (class "Default")
      (node (ref "U1") (pin "51") (pinfunction "PB12_51") (pintype "bidirectional"))
    )
    (net (code "157") (name "unconnected-(U1-PB13-Pad52)") (class "Default")
      (node (ref "U1") (pin "52") (pinfunction "PB13_52") (pintype "bidirectional"))
    )
    (net (code "158") (name "unconnected-(U1-PB14-Pad53)") (class "Default")
      (node (ref "U1") (pin "53") (pinfunction "PB14_53") (pintype "bidirectional"))
    )
    (net (code "159") (name "unconnected-(U1-PB15-Pad54)") (class "Default")
      (node (ref "U1") (pin "54") (pinfunction "PB15_54") (pintype "bidirectional"))
    )
    (net (code "160") (name "unconnected-(U1-PC5-Pad34)") (class "Default")
      (node (ref "U1") (pin "34") (pinfunction "PC5_34") (pintype "bidirectional"))
    )
    (net (code "161") (name "unconnected-(U1-PC8-Pad65)") (class "Default")
      (node (ref "U1") (pin "65") (pinfunction "PC8_65") (pintype "bidirectional"))
    )
    (net (code "162") (name "unconnected-(U1-PD0-Pad81)") (class "Default")
      (node (ref "U1") (pin "81") (pinfunction "PD0_81") (pintype "bidirectional"))
    )
    (net (code "163") (name "unconnected-(U1-PD1-Pad82)") (class "Default")
      (node (ref "U1") (pin "82") (pinfunction "PD1_82") (pintype "bidirectional"))
    )
    (net (code "164") (name "unconnected-(U1-PD3-Pad84)") (class "Default")
      (node (ref "U1") (pin "84") (pinfunction "PD3_84") (pintype "bidirectional"))
    )
    (net (code "165") (name "unconnected-(U1-PD4-Pad85)") (class "Default")
      (node (ref "U1") (pin "85") (pinfunction "PD4_85") (pintype "bidirectional"))
    )
    (net (code "166") (name "unconnected-(U1-PD5-Pad86)") (class "Default")
      (node (ref "U1") (pin "86") (pinfunction "PD5_86") (pintype "bidirectional"))
    )
    (net (code "167") (name "unconnected-(U1-PD6-Pad87)") (class "Default")
      (node (ref "U1") (pin "87") (pinfunction "PD6_87") (pintype "bidirectional"))
    )
    (net (code "168") (name "unconnected-(U1-PD7-Pad88)") (class "Default")
      (node (ref "U1") (pin "88") (pinfunction "PD7_88") (pintype "bidirectional"))
    )
    (net (code "169") (name "unconnected-(U1-PD11-Pad58)") (class "Default")
      (node (ref "U1") (pin "58") (pinfunction "PD11_58") (pintype "bidirectional"))
    )
    (net (code "170") (name "unconnected-(U1-PE0-Pad97)") (class "Default")
      (node (ref "U1") (pin "97") (pinfunction "PE0_97") (pintype "bidirectional"))
    )
    (net (code "171") (name "unconnected-(U1-PE1-Pad98)") (class "Default")
      (node (ref "U1") (pin "98") (pinfunction "PE1_98") (pintype "bidirectional"))
    )
    (net (code "172") (name "unconnected-(U1-PE7-Pad38)") (class "Default")
      (node (ref "U1") (pin "38") (pinfunction "PE7_38") (pintype "bidirectional"))
    )
    (net (code "173") (name "unconnected-(U1-PE8-Pad39)") (class "Default")
      (node (ref "U1") (pin "39") (pinfunction "PE8_39") (pintype "bidirectional"))
    )
    (net (code "174") (name "unconnected-(U1-PE9-Pad40)") (class "Default")
      (node (ref "U1") (pin "40") (pinfunction "PE9_40") (pintype "bidirectional"))
    )
    (net (code "175") (name "unconnected-(U1-PE10-Pad41)") (class "Default")
      (node (ref "U1") (pin "41") (pinfunction "PE10_41") (pintype "bidirectional"))
    )
    (net (code "176") (name "unconnected-(U1-PE11-Pad42)") (class "Default")
      (node (ref "U1") (pin "42") (pinfunction "PE11_42") (pintype "bidirectional"))
    )
    (net (code "177") (name "unconnected-(U1-PE12-Pad43)") (class "Default")
      (node (ref "U1") (pin "43") (pinfunction "PE12_43") (pintype "bidirectional"))
    )
    (net (code "178") (name "unconnected-(U1-PE13-Pad44)") (class "Default")
      (node (ref "U1") (pin "44") (pinfunction "PE13_44") (pintype "bidirectional"))
    )
    (net (code "179") (name "unconnected-(U1-PE14-Pad45)") (class "Default")
      (node (ref "U1") (pin "45") (pinfunction "PE14_45") (pintype "bidirectional"))
    )
    (net (code "180") (name "unconnected-(U1-PE15-Pad46)") (class "Default")
      (node (ref "U1") (pin "46") (pinfunction "PE15_46") (pintype "bidirectional"))
    )
    (net (code "181") (name "unconnected-(U3-IO0-Pad12)") (class "Default")
      (node (ref "U3") (pin "12") (pinfunction "IO0_12") (pintype "passive"))
    )
    (net (code "182") (name "unconnected-(U3-IO1-Pad13)") (class "Default")
      (node (ref "U3") (pin "13") (pinfunction "IO1_13") (pintype "passive"))
    )
    (net (code "183") (name "unconnected-(U3-IO2-Pad5)") (class "Default")
      (node (ref "U3") (pin "5") (pinfunction "IO2_5") (pintype "passive"))
    )
    (net (code "184") (name "unconnected-(U3-IO3-Pad6)") (class "Default")
      (node (ref "U3") (pin "6") (pinfunction "IO3_6") (pintype "passive"))
    )
    (net (code "185") (name "unconnected-(U3-IO4-Pad18)") (class "Default")
      (node (ref "U3") (pin "18") (pinfunction "IO4_18") (pintype "passive"))
    )
    (net (code "186") (name "unconnected-(U3-IO5-Pad19)") (class "Default")
      (node (ref "U3") (pin "19") (pinfunction "IO5_19") (pintype "passive"))
    )
    (net (code "187") (name "unconnected-(U3-IO6-Pad20)") (class "Default")
      (node (ref "U3") (pin "20") (pinfunction "IO6_20") (pintype "passive"))
    )
    (net (code "188") (name "unconnected-(U3-IO7-Pad21)") (class "Default")
      (node (ref "U3") (pin "21") (pinfunction "IO7_21") (pintype "passive"))
    )
    (net (code "189") (name "unconnected-(U3-IO8-Pad22)") (class "Default")
      (node (ref "U3") (pin "22") (pinfunction "IO8_22") (pintype "passive"))
    )
    (net (code "190") (name "unconnected-(U3-IO9-Pad23)") (class "Default")
      (node (ref "U3") (pin "23") (pinfunction "IO9_23") (pintype "passive"))
    )
    (net (code "191") (name "unconnected-(U3-IO10-Pad16)") (class "Default")
      (node (ref "U3") (pin "16") (pinfunction "IO10_16") (pintype "passive"))
    )
    (net (code "192") (name "unconnected-(U3-NC-Pad4)") (class "Default")
      (node (ref "U3") (pin "4") (pinfunction "NC_4") (pintype "passive+no_connect"))
    )
    (net (code "193") (name "unconnected-(U3-NC-Pad7)") (class "Default")
      (node (ref "U3") (pin "7") (pinfunction "NC_7") (pintype "passive+no_connect"))
    )
    (net (code "194") (name "unconnected-(U3-NC-Pad9)") (class "Default")
      (node (ref "U3") (pin "9") (pinfunction "NC_9") (pintype "passive+no_connect"))
    )
    (net (code "195") (name "unconnected-(U3-NC-Pad10)") (class "Default")
      (node (ref "U3") (pin "10") (pinfunction "NC_10") (pintype "passive+no_connect"))
    )
    (net (code "196") (name "unconnected-(U3-NC-Pad15)") (class "Default")
      (node (ref "U3") (pin "15") (pinfunction "NC_15") (pintype "passive+no_connect"))
    )
    (net (code "197") (name "unconnected-(U3-NC-Pad17)") (class "Default")
      (node (ref "U3") (pin "17") (pinfunction "NC_17") (pintype "passive+no_connect"))
    )
    (net (code "198") (name "unconnected-(U3-NC-Pad24)") (class "Default")
      (node (ref "U3") (pin "24") (pinfunction "NC_24") (pintype "passive+no_connect"))
    )
    (net (code "199") (name "unconnected-(U3-NC-Pad25)") (class "Default")
      (node (ref "U3") (pin "25") (pinfunction "NC_25") (pintype "passive+no_connect"))
    )
    (net (code "200") (name "unconnected-(U3-NC-Pad28)") (class "Default")
      (node (ref "U3") (pin "28") (pinfunction "NC_28") (pintype "passive+no_connect"))
    )
    (net (code "201") (name "unconnected-(U3-NC-Pad29)") (class "Default")
      (node (ref "U3") (pin "29") (pinfunction "NC_29") (pintype "passive+no_connect"))
    )
    (net (code "202") (name "unconnected-(U3-NC-Pad32)") (class "Default")
      (node (ref "U3") (pin "32") (pinfunction "NC_32") (pintype "passive+no_connect"))
    )
    (net (code "203") (name "unconnected-(U3-NC-Pad33)") (class "Default")
      (node (ref "U3") (pin "33") (pinfunction "NC_33") (pintype "passive+no_connect"))
    )
    (net (code "204") (name "unconnected-(U3-NC-Pad34)") (class "Default")
      (node (ref "U3") (pin "34") (pinfunction "NC_34") (pintype "passive+no_connect"))
    )
    (net (code "205") (name "unconnected-(U3-NC-Pad35)") (class "Default")
      (node (ref "U3") (pin "35") (pinfunction "NC_35") (pintype "passive+no_connect"))
    )
    (net (code "206") (name "unconnected-(U4-VREF-Pad5)") (class "Default")
      (node (ref "U4") (pin "5") (pinfunction "VREF_5") (pintype "passive"))
    )
  )
)
